# oresat-c3-v1_WRONG_FTDI.net
KiCad netlist of a schematic drawn in EAGLE
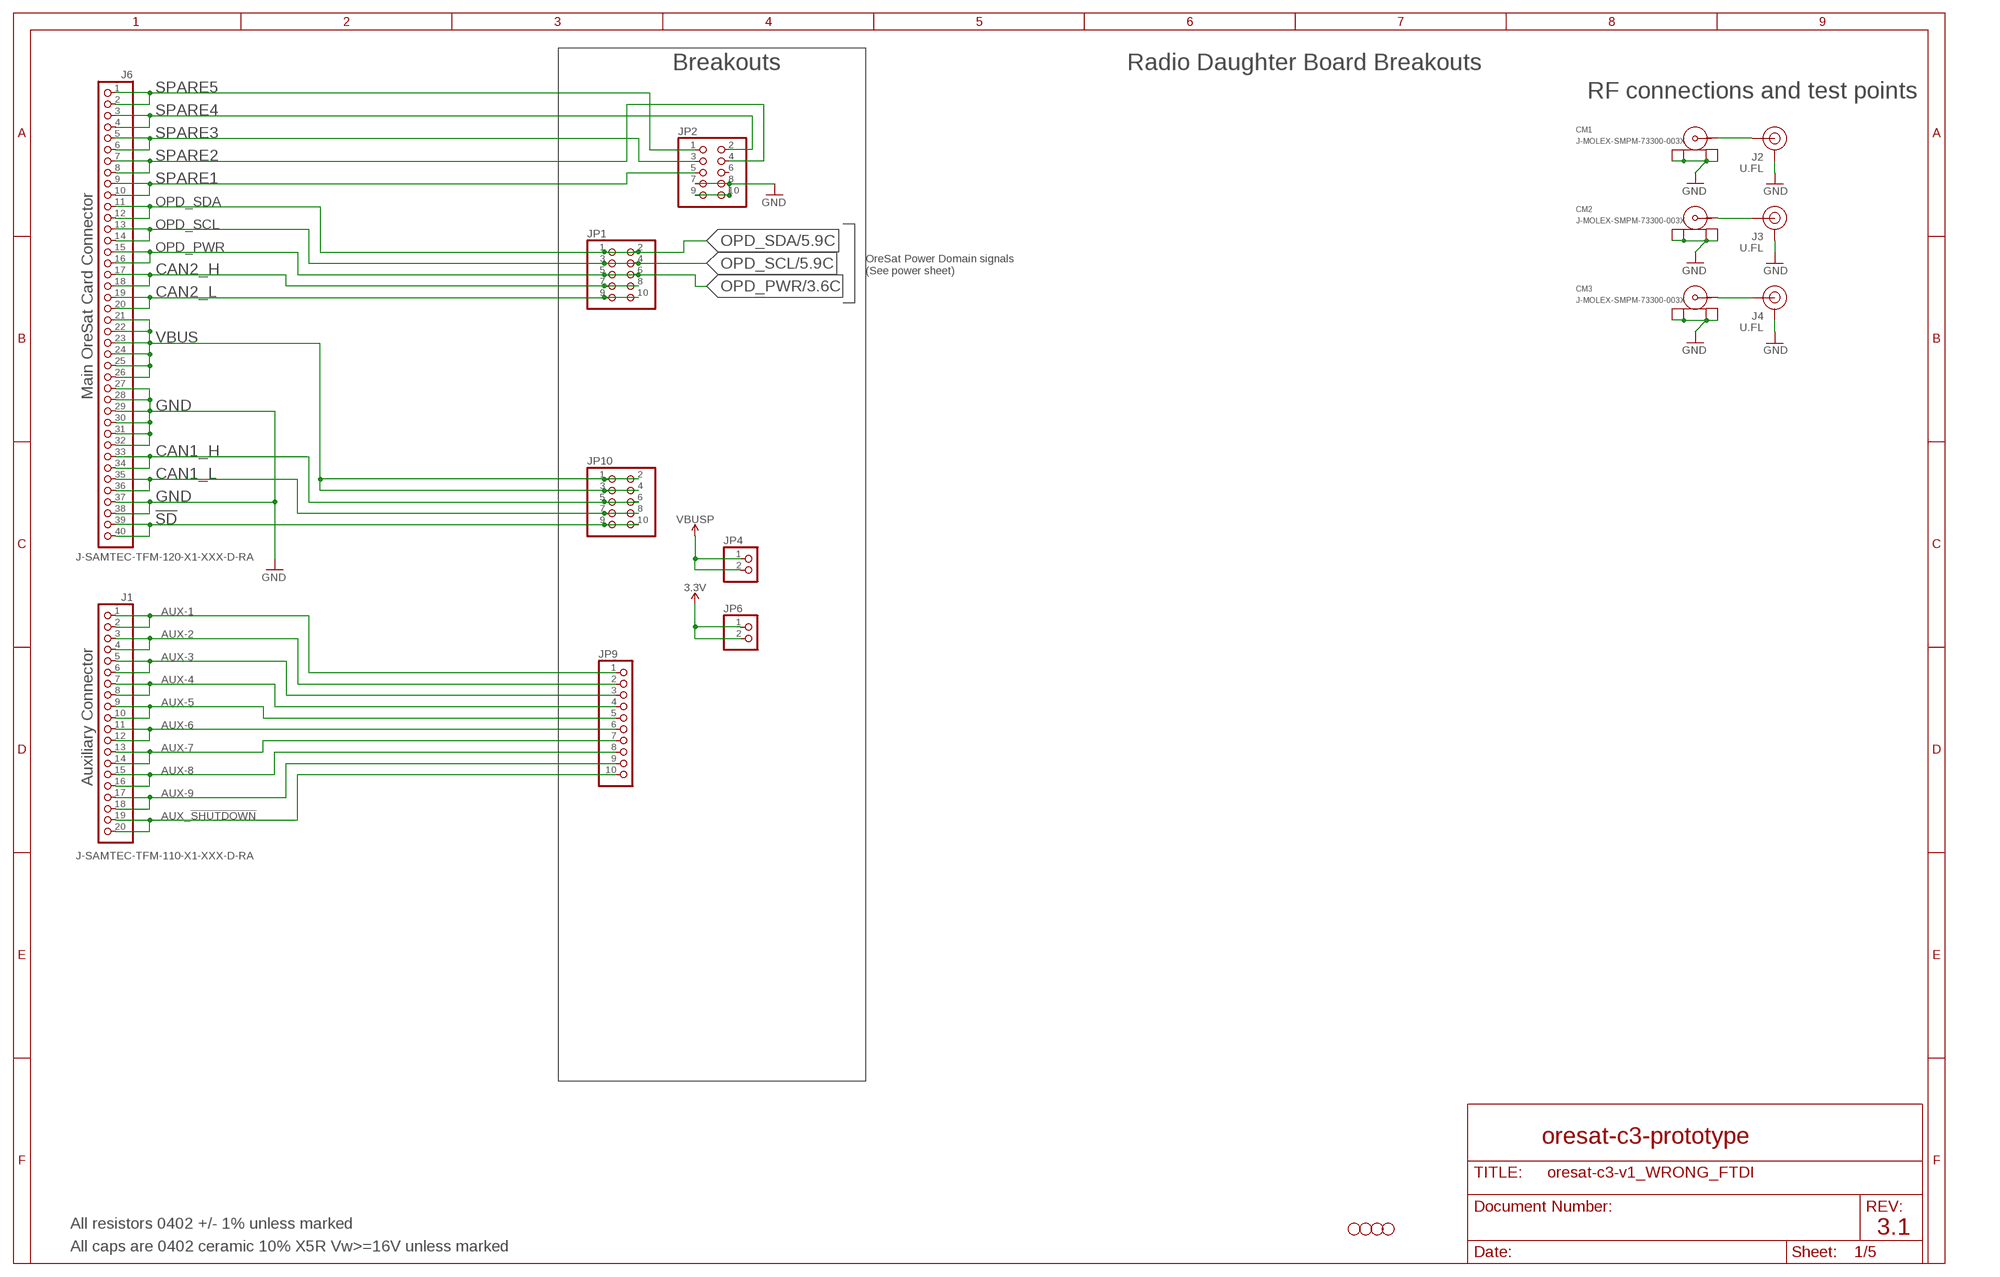
[diagram p0: schematic, sheet 1]
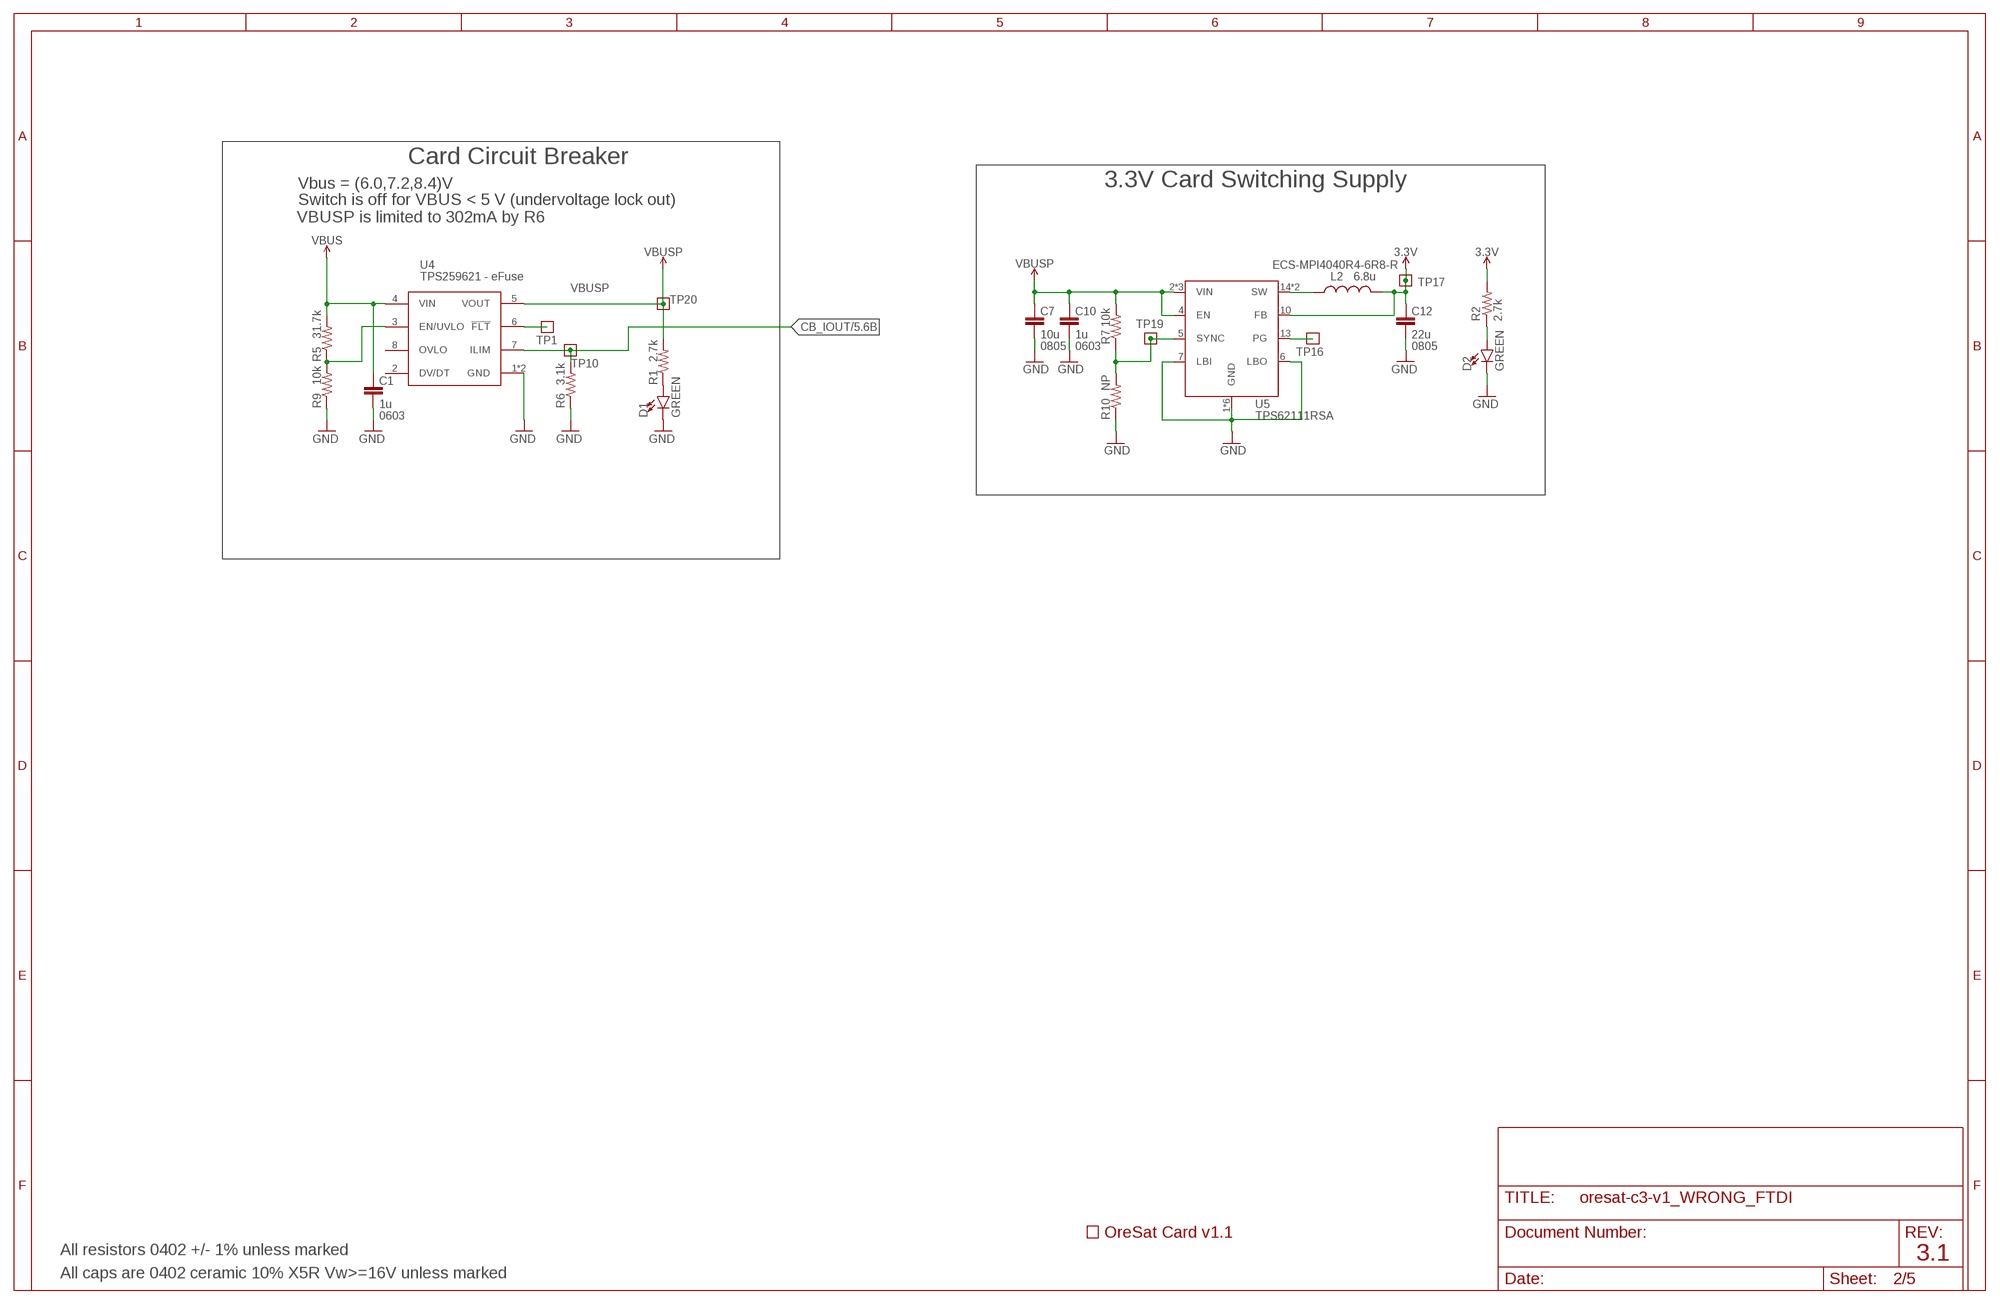
[diagram p1: schematic, sheet 2]
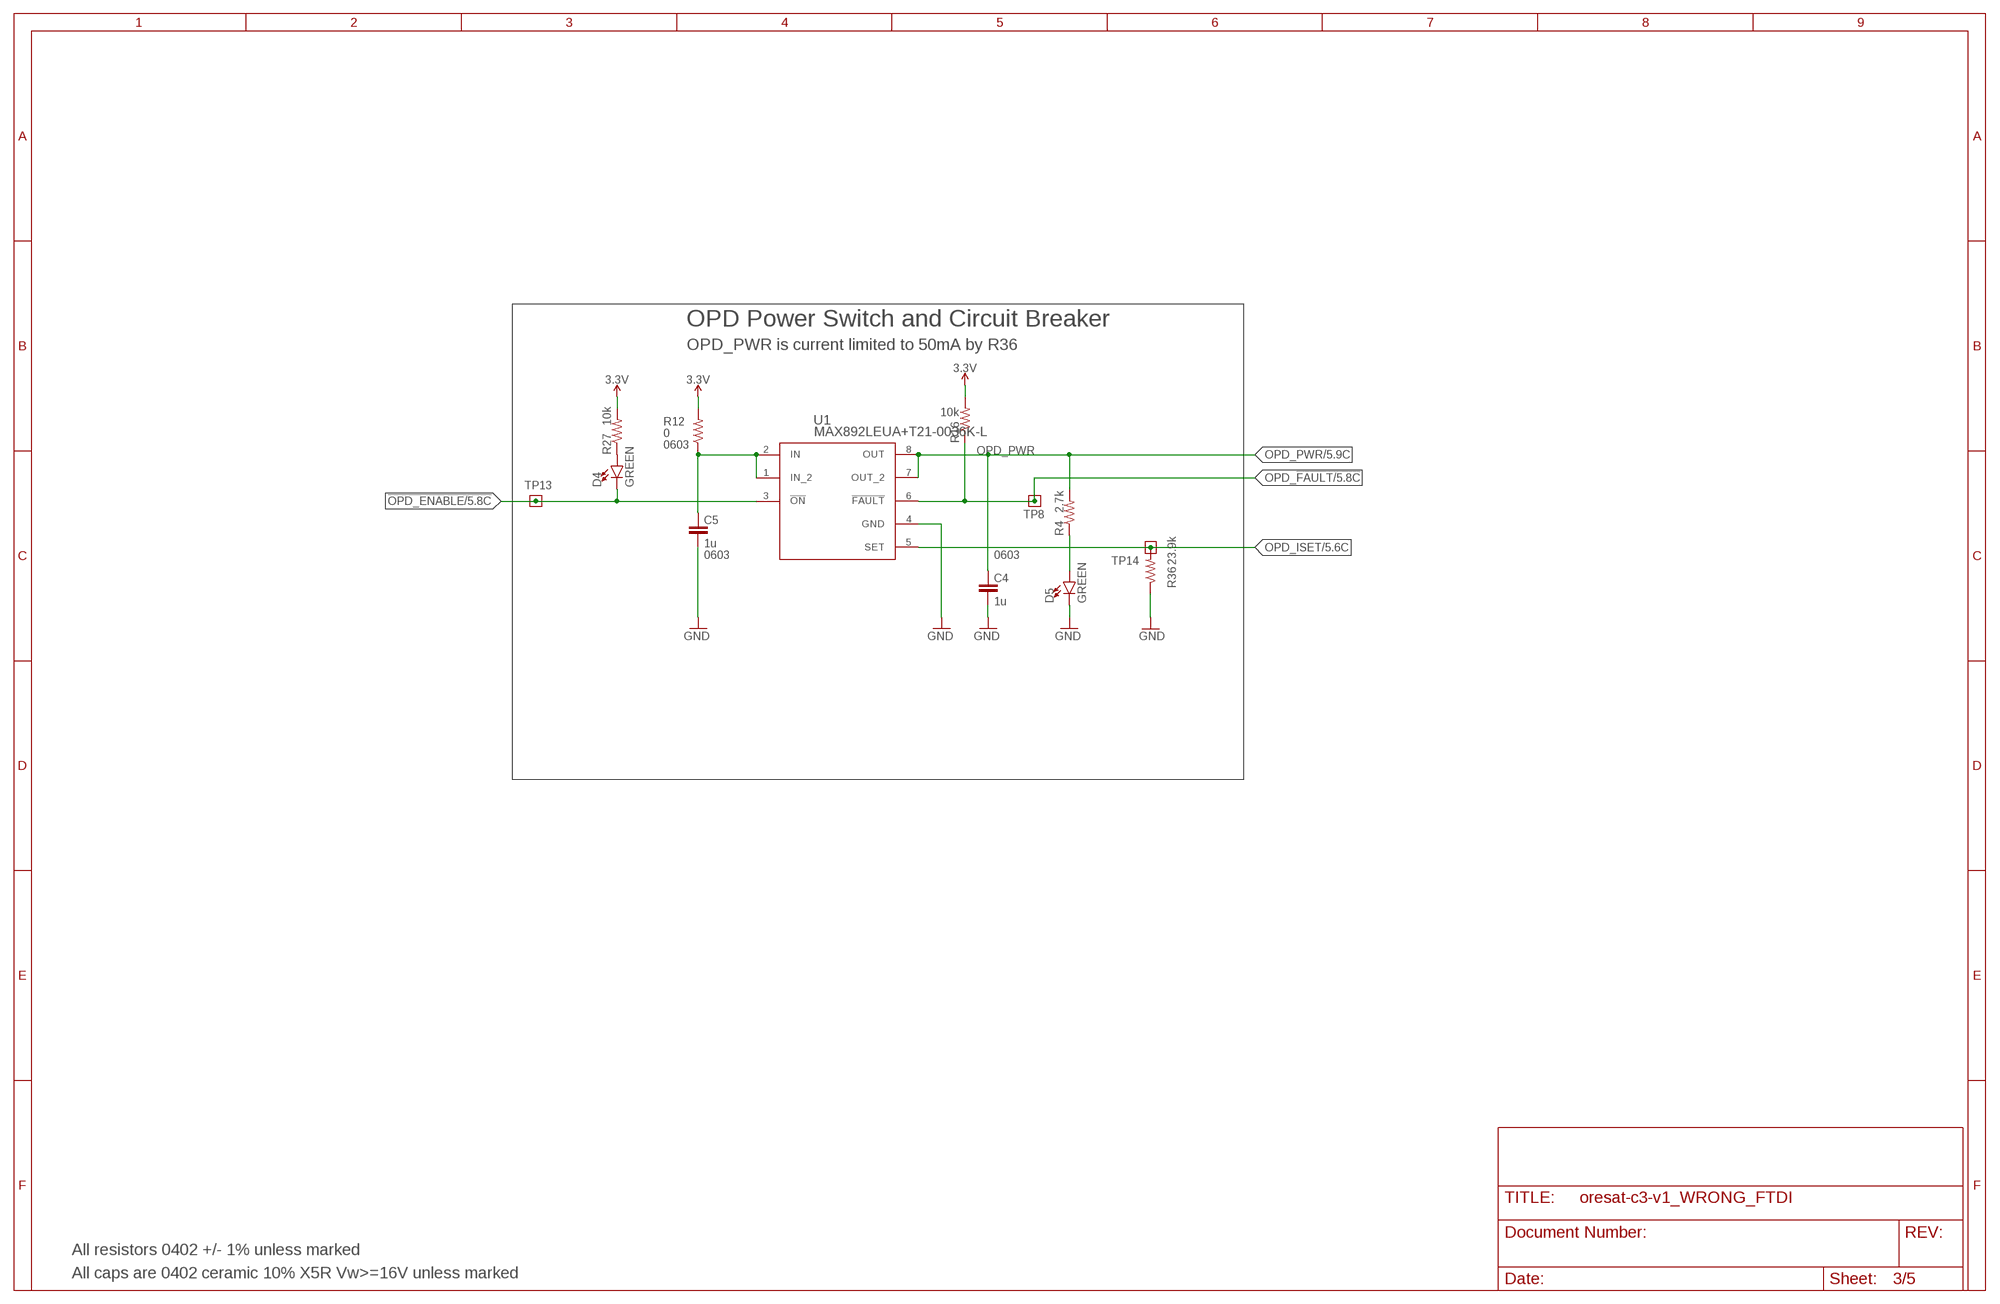
[diagram p2: schematic, sheet 3]
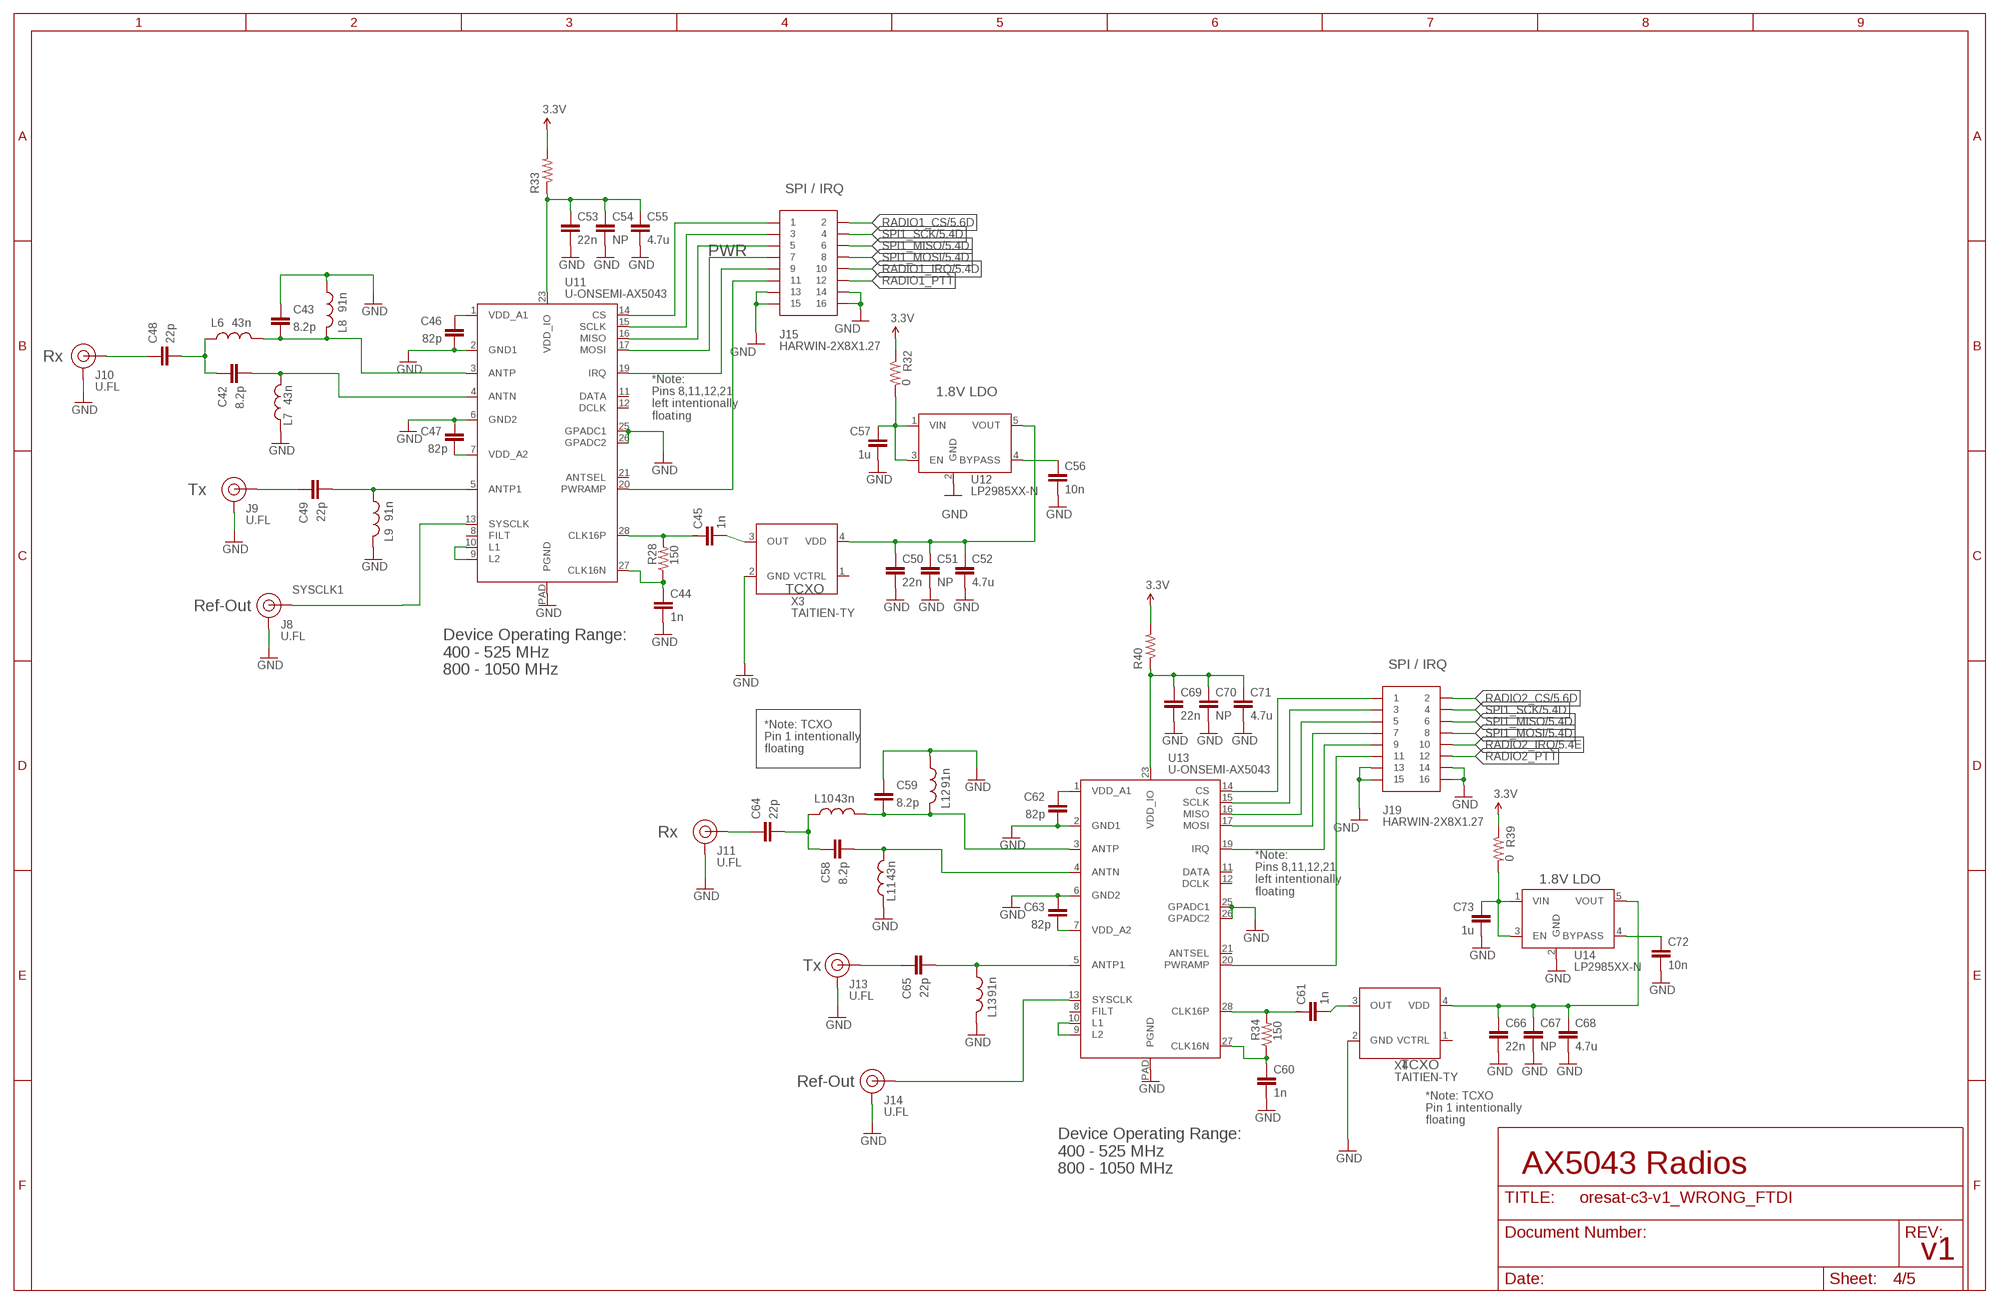
[diagram p3: schematic, sheet 4]
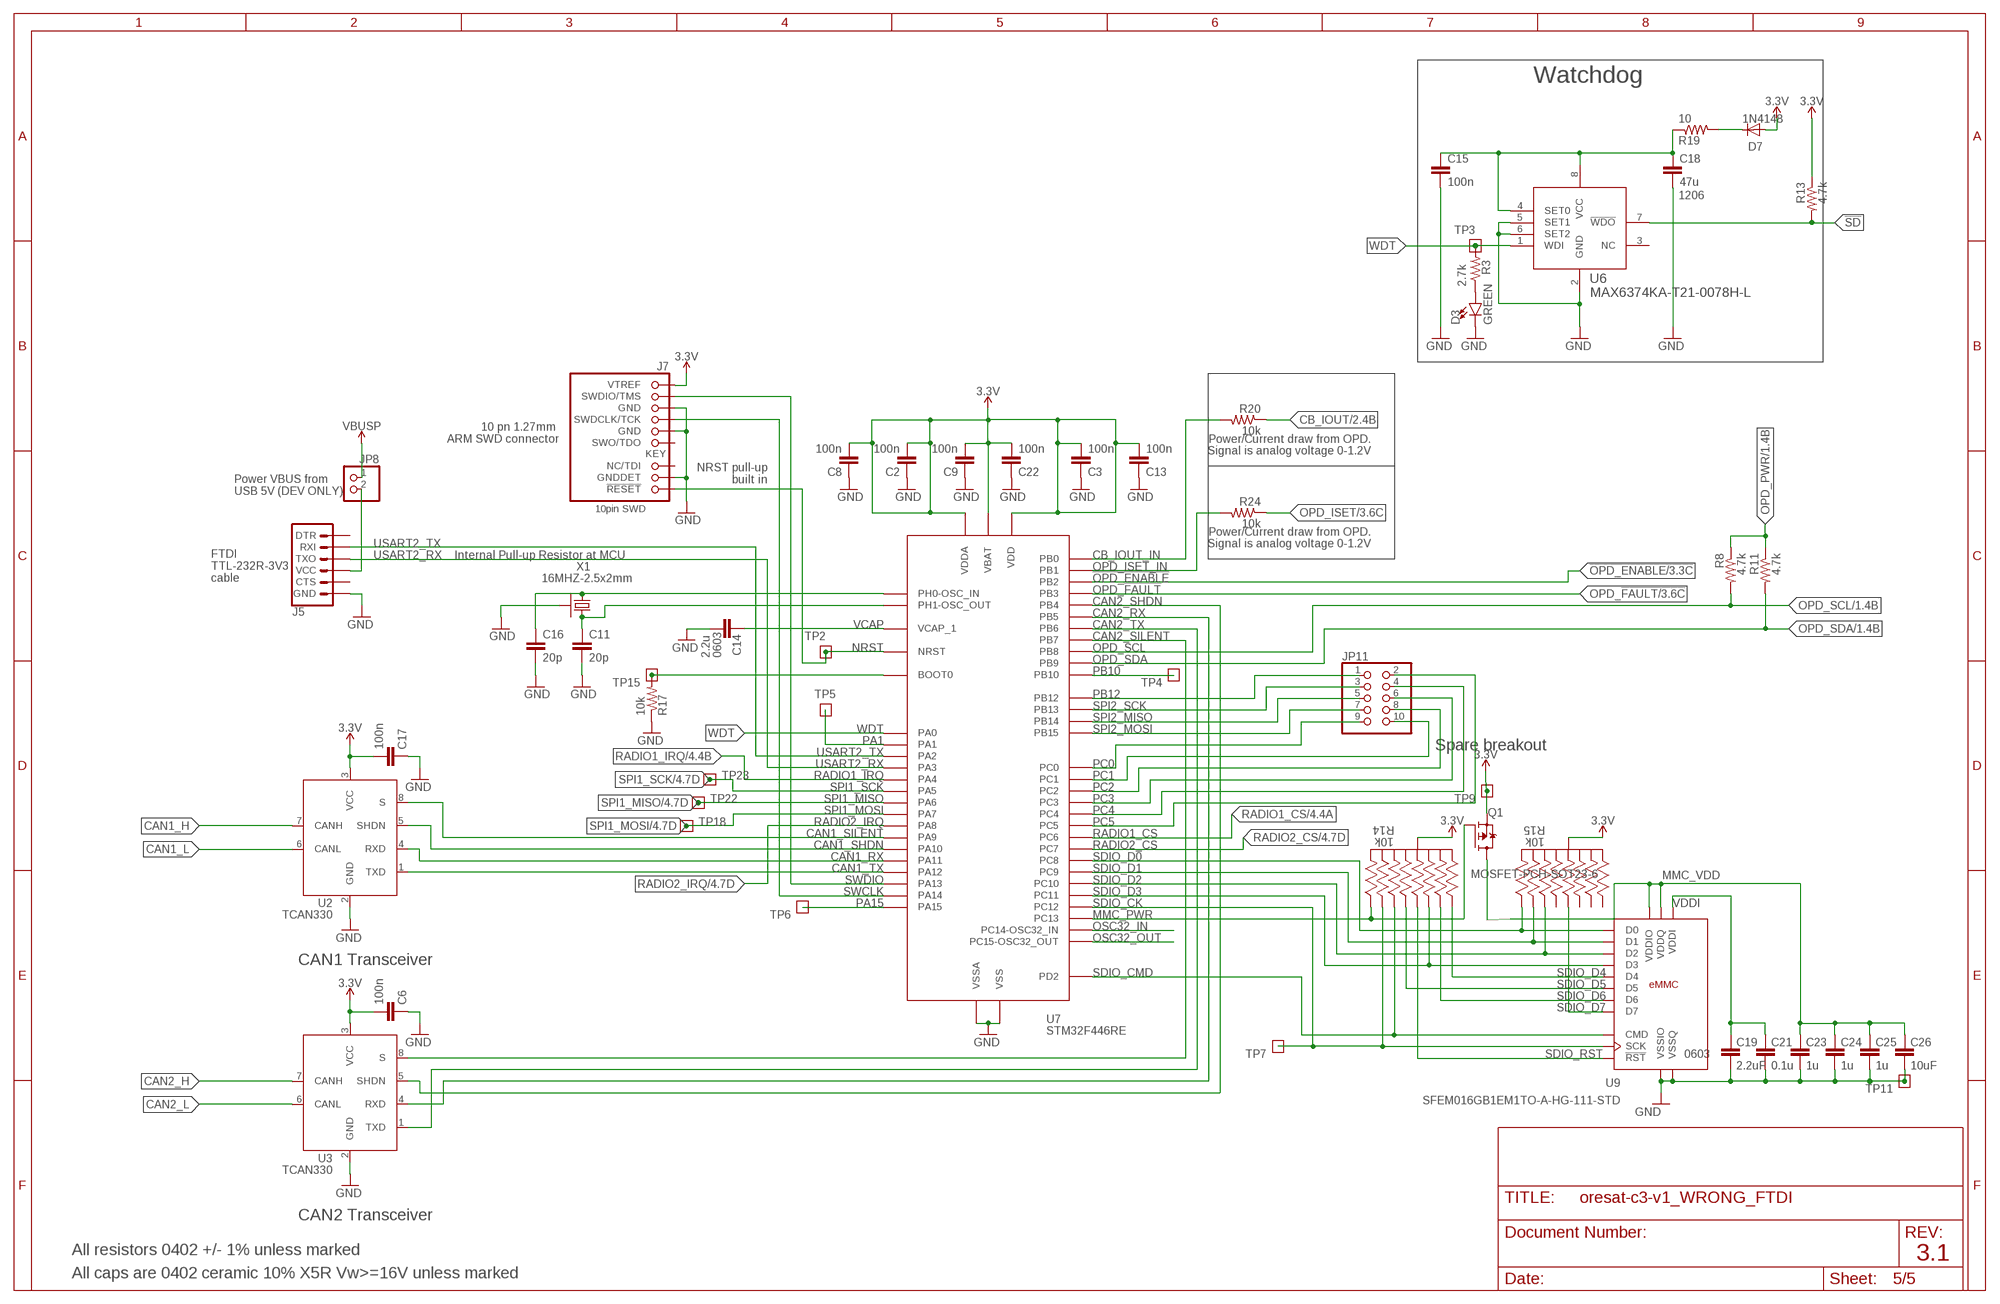
[diagram p4: schematic, sheet 5]

(export (version "E")
  (design (tool "Eeschema 10.0.6"))
  (components
    (comp (ref "C4")
      (value "1u")
      (footprint "eagle-import:.0603-B-NOSILK")
      (fields (field (name "MFR") "Samsung") (field (name "MPN") "CL05B104KO5NNNC"))
      (libsource (lib "eagle-import") (part "C-EU0603-B-NOSILK"))
    )
    (comp (ref "C5")
      (value "1u")
      (footprint "eagle-import:.0603-B-NOSILK")
      (fields (field (name "MFR") "Samsung") (field (name "MPN") "CL05B104KO5NNNC"))
      (libsource (lib "eagle-import") (part "C-EU0603-B-NOSILK"))
    )
    (comp (ref "D4")
      (value "GREEN")
      (footprint "eagle-import:LED-0603")
      (libsource (lib "eagle-import") (part "LED-GREEN0603"))
    )
    (comp (ref "D5")
      (value "GREEN")
      (footprint "eagle-import:LED-0603")
      (libsource (lib "eagle-import") (part "LED-GREEN0603"))
    )
    (comp (ref "R4")
      (value "2.7k")
      (footprint "eagle-import:.0402-B-NOSILK")
      (fields (field (name "MFR") "Samsung") (field (name "MPN") "RC1005F6653CS"))
      (libsource (lib "eagle-import") (part "R-US_0402-B-NOSILK"))
    )
    (comp (ref "R12")
      (value "0")
      (footprint "eagle-import:.0603-B-NOSILK")
      (fields (field (name "MFR") "Samsung") (field (name "MPN") "RC1005F6653CS"))
      (libsource (lib "eagle-import") (part "R-US_0603-B-NOSILK"))
    )
    (comp (ref "R16")
      (value "10k")
      (footprint "eagle-import:.0402-B-NOSILK")
      (fields (field (name "MFR") "Samsung") (field (name "MPN") "RC1005F6653CS"))
      (libsource (lib "eagle-import") (part "R-US_0402-B-NOSILK"))
    )
    (comp (ref "R27")
      (value "10k")
      (footprint "eagle-import:.0402-B-NOSILK")
      (fields (field (name "MFR") "Samsung") (field (name "MPN") "RC1005F6653CS"))
      (libsource (lib "eagle-import") (part "R-US_0402-B-NOSILK"))
    )
    (comp (ref "R36")
      (value "23.9k")
      (footprint "eagle-import:.0402-B-NOSILK")
      (fields (field (name "MFR") "Samsung") (field (name "MPN") "RC1005F6653CS"))
      (libsource (lib "eagle-import") (part "R-US_0402-B-NOSILK"))
    )
    (comp (ref "TP8")
      (value "TEST-POINT")
      (footprint "eagle-import:2MM-TEST-POINT")
      (libsource (lib "eagle-import") (part "TEST-POINT"))
    )
    (comp (ref "TP13")
      (value "TEST-POINT")
      (footprint "eagle-import:2MM-TEST-POINT")
      (libsource (lib "eagle-import") (part "TEST-POINT"))
    )
    (comp (ref "TP14")
      (value "TEST-POINT")
      (footprint "eagle-import:2MM-TEST-POINT")
      (libsource (lib "eagle-import") (part "TEST-POINT"))
    )
    (comp (ref "U1")
      (value "MAX892LEUA+T21-0036K-L")
      (footprint "eagle-import:21-0036K-L")
      (fields (field (name "MANUFACTURER_PART_NUMBER") "MAX892LEUA+T"))
      (libsource (lib "eagle-import") (part "MAX892LEUA+T21-0036K-L"))
    )
    (comp (ref "C1")
      (value "1u")
      (footprint "eagle-import:.0603-B-NOSILK")
      (fields (field (name "MFR") "Samsung") (field (name "MPN") "CL05B104KO5NNNC"))
      (libsource (lib "eagle-import") (part "C-EU0603-B-NOSILK"))
    )
    (comp (ref "C7")
      (value "10u")
      (footprint "eagle-import:.0805-B-NOSILK")
      (libsource (lib "eagle-import") (part "C-EU0805-B-NOSILK"))
    )
    (comp (ref "C10")
      (value "1u")
      (footprint "eagle-import:.0603-B-NOSILK")
      (fields (field (name "MFR") "Samsung") (field (name "MPN") "CL05B104KO5NNNC"))
      (libsource (lib "eagle-import") (part "C-EU0603-B-NOSILK"))
    )
    (comp (ref "C12")
      (value "22u")
      (footprint "eagle-import:.0805-B-NOSILK")
      (libsource (lib "eagle-import") (part "C-EU0805-B-NOSILK"))
    )
    (comp (ref "D1")
      (value "GREEN")
      (footprint "eagle-import:LED-0603")
      (libsource (lib "eagle-import") (part "LED-GREEN0603"))
    )
    (comp (ref "D2")
      (value "GREEN")
      (footprint "eagle-import:LED-0603")
      (libsource (lib "eagle-import") (part "LED-GREEN0603"))
    )
    (comp (ref "L2")
      (value "6.8u")
      (footprint "eagle-import:ECS-MPI4040")
      (fields (field (name "MFR") "ECS") (field (name "MPN") "ECS-MPI4040R4-6R8-R"))
      (libsource (lib "eagle-import") (part "L-ECS-MPI4040"))
    )
    (comp (ref "R1")
      (value "2.7k")
      (footprint "eagle-import:.0402-B-NOSILK")
      (fields (field (name "MFR") "Samsung") (field (name "MPN") "RC1005F6653CS"))
      (libsource (lib "eagle-import") (part "R-US_0402-B-NOSILK"))
    )
    (comp (ref "R2")
      (value "2.7k")
      (footprint "eagle-import:.0402-B-NOSILK")
      (fields (field (name "MFR") "Samsung") (field (name "MPN") "RC1005F6653CS"))
      (libsource (lib "eagle-import") (part "R-US_0402-B-NOSILK"))
    )
    (comp (ref "R5")
      (value "31.7k")
      (footprint "eagle-import:.0402-B-NOSILK")
      (fields (field (name "MFR") "Samsung") (field (name "MPN") "RC1005F6653CS"))
      (libsource (lib "eagle-import") (part "R-US_0402-B-NOSILK"))
    )
    (comp (ref "R6")
      (value "3.1k")
      (footprint "eagle-import:.0402-B-NOSILK")
      (fields (field (name "MFR") "Samsung") (field (name "MPN") "RC1005F6653CS"))
      (libsource (lib "eagle-import") (part "R-US_0402-B-NOSILK"))
    )
    (comp (ref "R7")
      (value "10k")
      (footprint "eagle-import:.0402-B-NOSILK")
      (fields (field (name "MFR") "Samsung") (field (name "MPN") "RC1005F6653CS"))
      (libsource (lib "eagle-import") (part "R-US_0402-B-NOSILK"))
    )
    (comp (ref "R9")
      (value "10k")
      (footprint "eagle-import:.0402-B-NOSILK")
      (fields (field (name "MFR") "Samsung") (field (name "MPN") "RC1005F6653CS"))
      (libsource (lib "eagle-import") (part "R-US_0402-B-NOSILK"))
    )
    (comp (ref "R10")
      (value "NP")
      (footprint "eagle-import:.0402-B-NOSILK")
      (fields (field (name "MFR") "Samsung") (field (name "MPN") "RC1005F6653CS"))
      (libsource (lib "eagle-import") (part "R-US_0402-B-NOSILK"))
    )
    (comp (ref "TP1")
      (value "TEST-POINT")
      (footprint "eagle-import:2MM-TEST-POINT")
      (libsource (lib "eagle-import") (part "TEST-POINT"))
    )
    (comp (ref "TP10")
      (value "TEST-POINT")
      (footprint "eagle-import:2MM-TEST-POINT")
      (libsource (lib "eagle-import") (part "TEST-POINT"))
    )
    (comp (ref "TP16")
      (value "TEST-POINT")
      (footprint "eagle-import:2MM-TEST-POINT")
      (libsource (lib "eagle-import") (part "TEST-POINT"))
    )
    (comp (ref "TP17")
      (value "TEST-POINT")
      (footprint "eagle-import:2MM-TEST-POINT")
      (libsource (lib "eagle-import") (part "TEST-POINT"))
    )
    (comp (ref "TP19")
      (value "TEST-POINT")
      (footprint "eagle-import:2MM-TEST-POINT")
      (libsource (lib "eagle-import") (part "TEST-POINT"))
    )
    (comp (ref "TP20")
      (value "TEST-POINT")
      (footprint "eagle-import:2MM-TEST-POINT")
      (libsource (lib "eagle-import") (part "TEST-POINT"))
    )
    (comp (ref "U$1")
      (value "ORESAT-CARD-V1.1-3XRF")
      (footprint "eagle-import:ORESAT-CARD-V1.1-3XRF")
      (libsource (lib "eagle-import") (part "ORESAT-CARD-V1.1-3XRF"))
    )
    (comp (ref "U4")
      (value "TPS259621 - eFuse")
      (footprint "eagle-import:SO-POWERPAD-8")
      (libsource (lib "eagle-import") (part "TPS2596XX"))
    )
    (comp (ref "U5")
      (value "TPS62111RSA")
      (footprint "eagle-import:S-PVQFN-16")
      (fields (field (name "MFR") "TI"))
      (libsource (lib "eagle-import") (part "TPS6211X"))
    )
    (comp (ref "CM1")
      (value "J-MOLEX-SMPM-73300-003X")
      (footprint "eagle-import:J-MOLEX-SMPM-073300-003X")
      (fields (field (name "MFR") "Molex") (field (name "MPN") "73300-0020"))
      (libsource (lib "eagle-import") (part "J-MOLEX-SMPM-73300-003X"))
    )
    (comp (ref "CM2")
      (value "J-MOLEX-SMPM-73300-003X")
      (footprint "eagle-import:J-MOLEX-SMPM-073300-003X")
      (fields (field (name "MFR") "Molex") (field (name "MPN") "73300-0020"))
      (libsource (lib "eagle-import") (part "J-MOLEX-SMPM-73300-003X"))
    )
    (comp (ref "CM3")
      (value "J-MOLEX-SMPM-73300-003X")
      (footprint "eagle-import:J-MOLEX-SMPM-073300-003X")
      (fields (field (name "MFR") "Molex") (field (name "MPN") "73300-0020"))
      (libsource (lib "eagle-import") (part "J-MOLEX-SMPM-73300-003X"))
    )
    (comp (ref "H1")
      (value "STAND-OFFTIGHT")
      (footprint "eagle-import:STAND-OFF-TIGHT")
      (libsource (lib "eagle-import") (part "STAND-OFFTIGHT"))
    )
    (comp (ref "H2")
      (value "STAND-OFFTIGHT")
      (footprint "eagle-import:STAND-OFF-TIGHT")
      (libsource (lib "eagle-import") (part "STAND-OFFTIGHT"))
    )
    (comp (ref "H3")
      (value "STAND-OFFTIGHT")
      (footprint "eagle-import:STAND-OFF-TIGHT")
      (libsource (lib "eagle-import") (part "STAND-OFFTIGHT"))
    )
    (comp (ref "H4")
      (value "STAND-OFFTIGHT")
      (footprint "eagle-import:STAND-OFF-TIGHT")
      (libsource (lib "eagle-import") (part "STAND-OFFTIGHT"))
    )
    (comp (ref "J1")
      (value "J-SAMTEC-TFM-110-X1-XXX-D-RA")
      (footprint "eagle-import:J-SAMTEC-TFM-110-X1-XXX-D-RA")
      (fields (field (name "MFR") "Samtec") (field (name "MPN") "TFM-110-01-L-D-RA "))
      (libsource (lib "eagle-import") (part "J-SAMTEC-TFM-110-X1-XXX-D-RA"))
    )
    (comp (ref "J2")
      (value "U.FL")
      (footprint "eagle-import:U.FL")
      (libsource (lib "eagle-import") (part "U.FL2PIN"))
    )
    (comp (ref "J3")
      (value "U.FL")
      (footprint "eagle-import:U.FL")
      (libsource (lib "eagle-import") (part "U.FL2PIN"))
    )
    (comp (ref "J4")
      (value "U.FL")
      (footprint "eagle-import:U.FL")
      (libsource (lib "eagle-import") (part "U.FL2PIN"))
    )
    (comp (ref "J6")
      (value "J-SAMTEC-TFM-120-X1-XXX-D-RA")
      (footprint "eagle-import:J-SAMTEC-TFM-120-X1-XXX-D-RA")
      (fields (field (name "MFR") "Samtec") (field (name "MPN") "TFM-120-01-L-D-RA"))
      (libsource (lib "eagle-import") (part "J-SAMTEC-TFM-120-X1-XXX-D-RA"))
    )
    (comp (ref "JP1")
      (value "PINHD-2X5")
      (footprint "eagle-import:2X05")
      (libsource (lib "eagle-import") (part "PINHD-2X5"))
    )
    (comp (ref "JP2")
      (value "PINHD-2X5")
      (footprint "eagle-import:2X05")
      (libsource (lib "eagle-import") (part "PINHD-2X5"))
    )
    (comp (ref "JP4")
      (value "PINHD-1X2")
      (footprint "eagle-import:1X02")
      (libsource (lib "eagle-import") (part "PINHD-1X2"))
    )
    (comp (ref "JP6")
      (value "PINHD-1X2")
      (footprint "eagle-import:1X02")
      (libsource (lib "eagle-import") (part "PINHD-1X2"))
    )
    (comp (ref "JP9")
      (value "PINHD-1X10")
      (footprint "eagle-import:1X10")
      (libsource (lib "eagle-import") (part "PINHD-1X10"))
    )
    (comp (ref "JP10")
      (value "PINHD-2X5")
      (footprint "eagle-import:2X05")
      (libsource (lib "eagle-import") (part "PINHD-2X5"))
    )
    (comp (ref "C2")
      (value "100n")
      (footprint "eagle-import:.0402-B-NOSILK")
      (fields (field (name "MFR") "Samsung") (field (name "MPN") "CL05B104KO5NNNC"))
      (libsource (lib "eagle-import") (part "C-EU0402-B-NOSILK"))
    )
    (comp (ref "C3")
      (value "100n")
      (footprint "eagle-import:.0402-B-NOSILK")
      (fields (field (name "MFR") "Samsung") (field (name "MPN") "CL05B104KO5NNNC"))
      (libsource (lib "eagle-import") (part "C-EU0402-B-NOSILK"))
    )
    (comp (ref "C6")
      (value "100n")
      (footprint "eagle-import:.0402-B-NOSILK")
      (fields (field (name "MFR") "Samsung") (field (name "MPN") "CL05B104KO5NNNC"))
      (libsource (lib "eagle-import") (part "C-EU0402-B-NOSILK"))
    )
    (comp (ref "C8")
      (value "100n")
      (footprint "eagle-import:.0402-B-NOSILK")
      (fields (field (name "MFR") "Samsung") (field (name "MPN") "CL05B104KO5NNNC"))
      (libsource (lib "eagle-import") (part "C-EU0402-B-NOSILK"))
    )
    (comp (ref "C9")
      (value "100n")
      (footprint "eagle-import:.0402-B-NOSILK")
      (fields (field (name "MFR") "Samsung") (field (name "MPN") "CL05B104KO5NNNC"))
      (libsource (lib "eagle-import") (part "C-EU0402-B-NOSILK"))
    )
    (comp (ref "C11")
      (value "20p")
      (footprint "eagle-import:.0402-B-NOSILK")
      (fields (field (name "MFR") "Samsung") (field (name "MPN") "CL05C200JB51PNC"))
      (libsource (lib "eagle-import") (part "rcl_custom_C-EU0402-B-NOSILK"))
    )
    (comp (ref "C13")
      (value "100n")
      (footprint "eagle-import:.0402-B-NOSILK")
      (fields (field (name "MFR") "Samsung") (field (name "MPN") "CL05B104KO5NNNC"))
      (libsource (lib "eagle-import") (part "C-EU0402-B-NOSILK"))
    )
    (comp (ref "C14")
      (value "2.2u")
      (footprint "eagle-import:.0603-B-NOSILK")
      (fields (field (name "MFR") "Samsung") (field (name "MPN") "CL05B104KO5NNNC"))
      (libsource (lib "eagle-import") (part "C-EU0603-B-NOSILK"))
    )
    (comp (ref "C15")
      (value "100n")
      (footprint "eagle-import:.0402-B-NOSILK")
      (fields (field (name "MFR") "Samsung") (field (name "MPN") "CL05C200JB51PNC"))
      (libsource (lib "eagle-import") (part "C-EU0402-B-NOSILK"))
    )
    (comp (ref "C16")
      (value "20p")
      (footprint "eagle-import:.0402-B-NOSILK")
      (fields (field (name "MFR") "Samsung") (field (name "MPN") "CL05C200JB51PNC"))
      (libsource (lib "eagle-import") (part "C-EU0402-B-NOSILK"))
    )
    (comp (ref "C17")
      (value "100n")
      (footprint "eagle-import:.0402-B-NOSILK")
      (fields (field (name "MFR") "Samsung") (field (name "MPN") "CL05B104KO5NNNC"))
      (libsource (lib "eagle-import") (part "C-EU0402-B-NOSILK"))
    )
    (comp (ref "C18")
      (value "47u")
      (footprint "eagle-import:1206-B")
      (fields (field (name "MFR") "Samsung") (field (name "MPN") "CL05C200JB51PNC"))
      (libsource (lib "eagle-import") (part "C-EU1206-B"))
    )
    (comp (ref "C19")
      (value "2.2uF")
      (footprint "eagle-import:.0603-B-NOSILK")
      (fields (field (name "MFR") "Samsung") (field (name "MPN") "CL05B104KO5NNNC"))
      (libsource (lib "eagle-import") (part "C-EU0603-B-NOSILK"))
    )
    (comp (ref "C21")
      (value "0.1u")
      (footprint "eagle-import:.0603-B-NOSILK")
      (fields (field (name "MFR") "Samsung") (field (name "MPN") "CL05B104KO5NNNC"))
      (libsource (lib "eagle-import") (part "C-EU0603-B-NOSILK"))
    )
    (comp (ref "C22")
      (value "100n")
      (footprint "eagle-import:.0402-B-NOSILK")
      (fields (field (name "MFR") "Samsung") (field (name "MPN") "CL05B104KO5NNNC"))
      (libsource (lib "eagle-import") (part "C-EU0402-B-NOSILK"))
    )
    (comp (ref "C23")
      (value "1u")
      (footprint "eagle-import:.0603-B-NOSILK")
      (fields (field (name "MFR") "Samsung") (field (name "MPN") "CL05B104KO5NNNC"))
      (libsource (lib "eagle-import") (part "C-EU0603-B-NOSILK"))
    )
    (comp (ref "C24")
      (value "1u")
      (footprint "eagle-import:.0603-B-NOSILK")
      (fields (field (name "MFR") "Samsung") (field (name "MPN") "CL05B104KO5NNNC"))
      (libsource (lib "eagle-import") (part "C-EU0603-B-NOSILK"))
    )
    (comp (ref "C25")
      (value "1u")
      (footprint "eagle-import:.0603-B-NOSILK")
      (fields (field (name "MFR") "Samsung") (field (name "MPN") "CL05B104KO5NNNC"))
      (libsource (lib "eagle-import") (part "C-EU0603-B-NOSILK"))
    )
    (comp (ref "C26")
      (value "10uF")
      (footprint "eagle-import:.0603-B-NOSILK")
      (fields (field (name "MFR") "Samsung") (field (name "MPN") "CL05B104KO5NNNC"))
      (libsource (lib "eagle-import") (part "C-EU0603-B-NOSILK"))
    )
    (comp (ref "D3")
      (value "GREEN")
      (footprint "eagle-import:LED-0603")
      (libsource (lib "eagle-import") (part "LED-GREEN0603"))
    )
    (comp (ref "D7")
      (value "1N4148")
      (footprint "eagle-import:SOD-323")
      (libsource (lib "eagle-import") (part "DIODESOD"))
    )
    (comp (ref "J5")
      (value "6_PIN_SERIAL_TARGETSILK")
      (footprint "eagle-import:6_PIN_SERIAL_TARGET_SIDE_W_SILK")
      (libsource (lib "eagle-import") (part "6_PIN_SERIAL_TARGETSILK"))
    )
    (comp (ref "J7")
      (value "FTSH-105-XX-X-DV-K")
      (footprint "eagle-import:CON10_2X5_DUK_FTSH")
      (fields (field (name "MFR") "Samtec") (field (name "MPN") "FTSH-105-01-F-DV-K"))
      (libsource (lib "eagle-import") (part "FTSH-105-XX-X-DV-K"))
    )
    (comp (ref "JP8")
      (value "PINHD-1X2")
      (footprint "eagle-import:1X02")
      (libsource (lib "eagle-import") (part "pinhead_325_PINHD-1X2"))
    )
    (comp (ref "JP11")
      (value "PINHD-2X5")
      (footprint "eagle-import:2X05")
      (libsource (lib "eagle-import") (part "PINHD-2X5"))
    )
    (comp (ref "Q1")
      (value "MOSFET-PCH-SOT23-6")
      (footprint "eagle-import:SOT23-6")
      (libsource (lib "eagle-import") (part "MOSFET-PCH-SOT23-6"))
    )
    (comp (ref "R3")
      (value "2.7k")
      (footprint "eagle-import:.0402-B-NOSILK")
      (fields (field (name "MFR") "Samsung") (field (name "MPN") "RC1005F6653CS"))
      (libsource (lib "eagle-import") (part "R-US_0402-B-NOSILK"))
    )
    (comp (ref "R8")
      (value "4.7k")
      (footprint "eagle-import:.0402-B-NOSILK")
      (libsource (lib "eagle-import") (part "R-US_0402-B-NOSILK"))
    )
    (comp (ref "R11")
      (value "4.7k")
      (footprint "eagle-import:.0402-B-NOSILK")
      (libsource (lib "eagle-import") (part "R-US_0402-B-NOSILK"))
    )
    (comp (ref "R13")
      (value "4.7k")
      (footprint "eagle-import:.0402-B-NOSILK")
      (libsource (lib "eagle-import") (part "R-US_0402-B-NOSILK"))
    )
    (comp (ref "R14")
      (value "10k")
      (footprint "eagle-import:ARRAY_EXBA-M")
      (fields (field (name "MANUFACTURER_PART_NUMBER") "EXBA10P391J"))
      (libsource (lib "eagle-import") (part "EXB-A10P391JC_ARRAY_EXBA-M"))
    )
    (comp (ref "R15")
      (value "10k")
      (footprint "eagle-import:ARRAY_EXBA-M")
      (fields (field (name "MANUFACTURER_PART_NUMBER") "EXBA10P391J"))
      (libsource (lib "eagle-import") (part "EXB-A10P391JC_ARRAY_EXBA-M"))
    )
    (comp (ref "R17")
      (value "10k")
      (footprint "eagle-import:.0402-B-NOSILK")
      (fields (field (name "MFR") "Samsung") (field (name "MPN") "RC1005F6653CS"))
      (libsource (lib "eagle-import") (part "R-US_0402-B-NOSILK"))
    )
    (comp (ref "R19")
      (value "10")
      (footprint "eagle-import:.0402-B-NOSILK")
      (libsource (lib "eagle-import") (part "R-US_0402-B-NOSILK"))
    )
    (comp (ref "R20")
      (value "10k")
      (footprint "eagle-import:.0402-B-NOSILK")
      (libsource (lib "eagle-import") (part "R-US_0402-B-NOSILK"))
    )
    (comp (ref "R24")
      (value "10k")
      (footprint "eagle-import:.0402-B-NOSILK")
      (libsource (lib "eagle-import") (part "R-US_0402-B-NOSILK"))
    )
    (comp (ref "TP2")
      (value "TEST-POINT")
      (footprint "eagle-import:2MM-TEST-POINT")
      (libsource (lib "eagle-import") (part "TEST-POINT"))
    )
    (comp (ref "TP3")
      (value "TEST-POINT")
      (footprint "eagle-import:2MM-TEST-POINT")
      (libsource (lib "eagle-import") (part "TEST-POINT"))
    )
    (comp (ref "TP4")
      (value "TEST-POINT")
      (footprint "eagle-import:2MM-TEST-POINT")
      (libsource (lib "eagle-import") (part "TEST-POINT"))
    )
    (comp (ref "TP5")
      (value "TEST-POINT")
      (footprint "eagle-import:2MM-TEST-POINT")
      (libsource (lib "eagle-import") (part "TEST-POINT"))
    )
    (comp (ref "TP6")
      (value "TEST-POINT")
      (footprint "eagle-import:2MM-TEST-POINT")
      (libsource (lib "eagle-import") (part "TEST-POINT"))
    )
    (comp (ref "TP7")
      (value "TEST-POINT")
      (footprint "eagle-import:2MM-TEST-POINT")
      (libsource (lib "eagle-import") (part "TEST-POINT"))
    )
    (comp (ref "TP9")
      (value "TEST-POINT")
      (footprint "eagle-import:2MM-TEST-POINT")
      (libsource (lib "eagle-import") (part "TEST-POINT"))
    )
    (comp (ref "TP11")
      (value "TEST-POINT")
      (footprint "eagle-import:2MM-TEST-POINT")
      (libsource (lib "eagle-import") (part "TEST-POINT"))
    )
    (comp (ref "TP15")
      (value "TEST-POINT")
      (footprint "eagle-import:2MM-TEST-POINT")
      (libsource (lib "eagle-import") (part "TEST-POINT"))
    )
    (comp (ref "TP18")
      (value "TEST-POINT")
      (footprint "eagle-import:2MM-TEST-POINT")
      (libsource (lib "eagle-import") (part "TEST-POINT"))
    )
    (comp (ref "TP22")
      (value "TEST-POINT")
      (footprint "eagle-import:2MM-TEST-POINT")
      (libsource (lib "eagle-import") (part "TEST-POINT"))
    )
    (comp (ref "TP23")
      (value "TEST-POINT")
      (footprint "eagle-import:2MM-TEST-POINT")
      (libsource (lib "eagle-import") (part "TEST-POINT"))
    )
    (comp (ref "U2")
      (value "TCAN330")
      (footprint "eagle-import:SOT23-8_TI-DCN")
      (fields (field (name "MFR") "Texas Instruments") (field (name "MPN") "TCAN330GDCNT"))
      (libsource (lib "eagle-import") (part "TCAN330"))
    )
    (comp (ref "U3")
      (value "TCAN330")
      (footprint "eagle-import:SOT23-8_TI-DCN")
      (fields (field (name "MFR") "Texas Instruments") (field (name "MPN") "TCAN330GDCNT"))
      (libsource (lib "eagle-import") (part "TCAN330"))
    )
    (comp (ref "U6")
      (value "MAX6374KA-T21-0078H-L")
      (footprint "eagle-import:21-0078H-L")
      (fields (field (name "MANUFACTURER_PART_NUMBER") "max6374kat"))
      (libsource (lib "eagle-import") (part "MAX6374KA-T21-0078H-L"))
    )
    (comp (ref "U7")
      (value "STM32F446RE")
      (footprint "eagle-import:QFP-10X10-64")
      (libsource (lib "eagle-import") (part "STM32F446RE"))
    )
    (comp (ref "U9")
      (value "SFEM016GB1EM1TO-A-HG-111-STD")
      (footprint "eagle-import:BGA-153(11.5X13)(EMMC-BA)")
      (libsource (lib "eagle-import") (part "EMMC+RESET-BA"))
    )
    (comp (ref "X1")
      (value "16MHZ-2.5x2mm")
      (footprint "eagle-import:CRYSTAL_2.5X2")
      (fields (field (name "MFR") "ECS Inc.") (field (name "MPN") "ECS-160-10-36Q-ES-TR"))
      (libsource (lib "eagle-import") (part "CRYSTAL-WITH-GND"))
    )
    (comp (ref "C42")
      (value "8.2p")
      (footprint "eagle-import:.0402-C-NOSILK")
      (libsource (lib "eagle-import") (part "C-EU0402-C-NOSILK"))
    )
    (comp (ref "C43")
      (value "8.2p")
      (footprint "eagle-import:.0402-C-NOSILK")
      (libsource (lib "eagle-import") (part "C-EU0402-C-NOSILK"))
    )
    (comp (ref "C44")
      (value "1n")
      (footprint "eagle-import:.0402-C-NOSILK")
      (libsource (lib "eagle-import") (part "C-EU0402-C-NOSILK"))
    )
    (comp (ref "C45")
      (value "1n")
      (footprint "eagle-import:.0402-C-NOSILK")
      (libsource (lib "eagle-import") (part "C-EU0402-C-NOSILK"))
    )
    (comp (ref "C46")
      (value "82p")
      (footprint "eagle-import:.0402-C-NOSILK")
      (libsource (lib "eagle-import") (part "C-EU0402-C-NOSILK"))
    )
    (comp (ref "C47")
      (value "82p")
      (footprint "eagle-import:.0402-C-NOSILK")
      (libsource (lib "eagle-import") (part "C-EU0402-C-NOSILK"))
    )
    (comp (ref "C48")
      (value "22p")
      (footprint "eagle-import:.0402-C-NOSILK")
      (libsource (lib "eagle-import") (part "C-EU0402-C-NOSILK"))
    )
    (comp (ref "C49")
      (value "22p")
      (footprint "eagle-import:.0402-C-NOSILK")
      (libsource (lib "eagle-import") (part "C-EU0402-C-NOSILK"))
    )
    (comp (ref "C50")
      (value "22n")
      (footprint "eagle-import:.0603-C-NOSILK")
      (libsource (lib "eagle-import") (part "C-EU0603-C-NOSILK"))
    )
    (comp (ref "C51")
      (value "NP")
      (footprint "eagle-import:.0603-C-NOSILK")
      (libsource (lib "eagle-import") (part "C-EU0603-C-NOSILK"))
    )
    (comp (ref "C52")
      (value "4.7u")
      (footprint "eagle-import:.0603-C-NOSILK")
      (libsource (lib "eagle-import") (part "C-EU0603-C-NOSILK"))
    )
    (comp (ref "C53")
      (value "22n")
      (footprint "eagle-import:.0603-C-NOSILK")
      (libsource (lib "eagle-import") (part "C-EU0603-C-NOSILK"))
    )
    (comp (ref "C54")
      (value "NP")
      (footprint "eagle-import:.0603-C-NOSILK")
      (libsource (lib "eagle-import") (part "C-EU0603-C-NOSILK"))
    )
    (comp (ref "C55")
      (value "4.7u")
      (footprint "eagle-import:.0603-C-NOSILK")
      (libsource (lib "eagle-import") (part "C-EU0603-C-NOSILK"))
    )
    (comp (ref "C56")
      (value "10n")
      (footprint "eagle-import:.0603-C-NOSILK")
      (libsource (lib "eagle-import") (part "C-EU0603-C-NOSILK"))
    )
    (comp (ref "C57")
      (value "1u")
      (footprint "eagle-import:.0603-C-NOSILK")
      (libsource (lib "eagle-import") (part "C-EU0603-C-NOSILK"))
    )
    (comp (ref "C58")
      (value "8.2p")
      (footprint "eagle-import:.0402-C-NOSILK")
      (libsource (lib "eagle-import") (part "C-EU0402-C-NOSILK"))
    )
    (comp (ref "C59")
      (value "8.2p")
      (footprint "eagle-import:.0402-C-NOSILK")
      (libsource (lib "eagle-import") (part "C-EU0402-C-NOSILK"))
    )
    (comp (ref "C60")
      (value "1n")
      (footprint "eagle-import:.0402-C-NOSILK")
      (libsource (lib "eagle-import") (part "C-EU0402-C-NOSILK"))
    )
    (comp (ref "C61")
      (value "1n")
      (footprint "eagle-import:.0402-C-NOSILK")
      (libsource (lib "eagle-import") (part "C-EU0402-C-NOSILK"))
    )
    (comp (ref "C62")
      (value "82p")
      (footprint "eagle-import:.0402-C-NOSILK")
      (libsource (lib "eagle-import") (part "C-EU0402-C-NOSILK"))
    )
    (comp (ref "C63")
      (value "82p")
      (footprint "eagle-import:.0402-C-NOSILK")
      (libsource (lib "eagle-import") (part "C-EU0402-C-NOSILK"))
    )
    (comp (ref "C64")
      (value "22p")
      (footprint "eagle-import:.0402-C-NOSILK")
      (libsource (lib "eagle-import") (part "C-EU0402-C-NOSILK"))
    )
    (comp (ref "C65")
      (value "22p")
      (footprint "eagle-import:.0402-C-NOSILK")
      (libsource (lib "eagle-import") (part "C-EU0402-C-NOSILK"))
    )
    (comp (ref "C66")
      (value "22n")
      (footprint "eagle-import:.0603-C-NOSILK")
      (libsource (lib "eagle-import") (part "C-EU0603-C-NOSILK"))
    )
    (comp (ref "C67")
      (value "NP")
      (footprint "eagle-import:.0603-C-NOSILK")
      (libsource (lib "eagle-import") (part "C-EU0603-C-NOSILK"))
    )
    (comp (ref "C68")
      (value "4.7u")
      (footprint "eagle-import:.0603-C-NOSILK")
      (libsource (lib "eagle-import") (part "C-EU0603-C-NOSILK"))
    )
    (comp (ref "C69")
      (value "22n")
      (footprint "eagle-import:.0603-C-NOSILK")
      (libsource (lib "eagle-import") (part "C-EU0603-C-NOSILK"))
    )
    (comp (ref "C70")
      (value "NP")
      (footprint "eagle-import:.0603-C-NOSILK")
      (libsource (lib "eagle-import") (part "C-EU0603-C-NOSILK"))
    )
    (comp (ref "C71")
      (value "4.7u")
      (footprint "eagle-import:.0603-C-NOSILK")
      (libsource (lib "eagle-import") (part "C-EU0603-C-NOSILK"))
    )
    (comp (ref "C72")
      (value "10n")
      (footprint "eagle-import:.0603-C-NOSILK")
      (libsource (lib "eagle-import") (part "C-EU0603-C-NOSILK"))
    )
    (comp (ref "C73")
      (value "1u")
      (footprint "eagle-import:.0603-C-NOSILK")
      (libsource (lib "eagle-import") (part "C-EU0603-C-NOSILK"))
    )
    (comp (ref "J8")
      (value "U.FL")
      (footprint "eagle-import:U.FL")
      (libsource (lib "eagle-import") (part "U.FL2PIN"))
    )
    (comp (ref "J9")
      (value "U.FL")
      (footprint "eagle-import:U.FL")
      (libsource (lib "eagle-import") (part "U.FL2PIN"))
    )
    (comp (ref "J10")
      (value "U.FL")
      (footprint "eagle-import:U.FL")
      (libsource (lib "eagle-import") (part "U.FL2PIN"))
    )
    (comp (ref "J11")
      (value "U.FL")
      (footprint "eagle-import:U.FL")
      (libsource (lib "eagle-import") (part "U.FL2PIN"))
    )
    (comp (ref "J13")
      (value "U.FL")
      (footprint "eagle-import:U.FL")
      (libsource (lib "eagle-import") (part "U.FL2PIN"))
    )
    (comp (ref "J14")
      (value "U.FL")
      (footprint "eagle-import:U.FL")
      (libsource (lib "eagle-import") (part "U.FL2PIN"))
    )
    (comp (ref "J15")
      (value "HARWIN-2X8X1.27")
      (footprint "eagle-import:2X8X1.27")
      (libsource (lib "eagle-import") (part "HARWIN-2X8X1.27"))
    )
    (comp (ref "J19")
      (value "HARWIN-2X8X1.27")
      (footprint "eagle-import:2X8X1.27")
      (libsource (lib "eagle-import") (part "HARWIN-2X8X1.27"))
    )
    (comp (ref "L6")
      (value "43n")
      (footprint "eagle-import:.0402-C-NOSILK")
      (libsource (lib "eagle-import") (part "L-US0402-C-NOSILK"))
    )
    (comp (ref "L7")
      (value "43n")
      (footprint "eagle-import:.0402-C-NOSILK")
      (libsource (lib "eagle-import") (part "L-US0402-C-NOSILK"))
    )
    (comp (ref "L8")
      (value "91n")
      (footprint "eagle-import:.0603-C-NOSILK")
      (libsource (lib "eagle-import") (part "L-US0603-C-NOSILK"))
    )
    (comp (ref "L9")
      (value "91n")
      (footprint "eagle-import:.0603-C-NOSILK")
      (libsource (lib "eagle-import") (part "L-US0603-C-NOSILK"))
    )
    (comp (ref "L10")
      (value "43n")
      (footprint "eagle-import:.0402-C-NOSILK")
      (libsource (lib "eagle-import") (part "L-US0402-C-NOSILK"))
    )
    (comp (ref "L11")
      (value "43n")
      (footprint "eagle-import:.0402-C-NOSILK")
      (libsource (lib "eagle-import") (part "L-US0402-C-NOSILK"))
    )
    (comp (ref "L12")
      (value "91n")
      (footprint "eagle-import:.0603-C-NOSILK")
      (libsource (lib "eagle-import") (part "L-US0603-C-NOSILK"))
    )
    (comp (ref "L13")
      (value "91n")
      (footprint "eagle-import:.0603-C-NOSILK")
      (libsource (lib "eagle-import") (part "L-US0603-C-NOSILK"))
    )
    (comp (ref "R28")
      (value "150")
      (footprint "eagle-import:.0402-C-NOSILK")
      (libsource (lib "eagle-import") (part "R-US_0402-C-NOSILK"))
    )
    (comp (ref "R32")
      (value "0")
      (footprint "eagle-import:.0603-C-NOSILK")
      (libsource (lib "eagle-import") (part "R-US_0603-C-NOSILK"))
    )
    (comp (ref "R33")
      (value "0")
      (footprint "eagle-import:.0603-C-NOSILK")
      (libsource (lib "eagle-import") (part "R-US_0603-C-NOSILK"))
    )
    (comp (ref "R34")
      (value "150")
      (footprint "eagle-import:.0402-C-NOSILK")
      (libsource (lib "eagle-import") (part "R-US_0402-C-NOSILK"))
    )
    (comp (ref "R39")
      (value "0")
      (footprint "eagle-import:.0603-C-NOSILK")
      (libsource (lib "eagle-import") (part "R-US_0603-C-NOSILK"))
    )
    (comp (ref "R40")
      (value "0")
      (footprint "eagle-import:.0603-C-NOSILK")
      (libsource (lib "eagle-import") (part "R-US_0603-C-NOSILK"))
    )
    (comp (ref "U11")
      (value "U-ONSEMI-AX5043")
      (footprint "eagle-import:QFN28-5X5-WITH-CENTER-PAD")
      (libsource (lib "eagle-import") (part "U-ONSEMI-AX5043"))
    )
    (comp (ref "U12")
      (value "LP2985XX-N")
      (footprint "eagle-import:SOT-23")
      (libsource (lib "eagle-import") (part "LP2985XX-N"))
    )
    (comp (ref "U13")
      (value "U-ONSEMI-AX5043")
      (footprint "eagle-import:QFN28-5X5-WITH-CENTER-PAD")
      (libsource (lib "eagle-import") (part "U-ONSEMI-AX5043"))
    )
    (comp (ref "U14")
      (value "LP2985XX-N")
      (footprint "eagle-import:SOT-23")
      (libsource (lib "eagle-import") (part "LP2985XX-N"))
    )
    (comp (ref "X3")
      (value "TAITIEN-TY")
      (footprint "eagle-import:2.5X2.0")
      (libsource (lib "eagle-import") (part "TAITIEN-TY"))
    )
    (comp (ref "X4")
      (value "TAITIEN-TY")
      (footprint "eagle-import:2.5X2.0")
      (libsource (lib "eagle-import") (part "TAITIEN-TY"))
    )
  )
  (nets
    (net (code "1") (name "3.3V") (class "Default")
      (node (ref "C12") (pin "1") (pinfunction "1_1") (pintype "passive"))
      (node (ref "C13") (pin "2") (pinfunction "2_2") (pintype "passive"))
      (node (ref "C17") (pin "2") (pinfunction "2_2") (pintype "passive"))
      (node (ref "C2") (pin "2") (pinfunction "2_2") (pintype "passive"))
      (node (ref "C22") (pin "2") (pinfunction "2_2") (pintype "passive"))
      (node (ref "C3") (pin "2") (pinfunction "2_2") (pintype "passive"))
      (node (ref "C6") (pin "2") (pinfunction "2_2") (pintype "passive"))
      (node (ref "C8") (pin "2") (pinfunction "2_2") (pintype "passive"))
      (node (ref "C9") (pin "2") (pinfunction "2_2") (pintype "passive"))
      (node (ref "D7") (pin "2") (pinfunction "A_2") (pintype "passive"))
      (node (ref "J7") (pin "1") (pinfunction "VTREF_1") (pintype "passive"))
      (node (ref "JP6") (pin "1") (pinfunction "1_1") (pintype "passive"))
      (node (ref "JP6") (pin "2") (pinfunction "2_2") (pintype "passive"))
      (node (ref "L2") (pin "2") (pinfunction "2_2") (pintype "passive"))
      (node (ref "Q1") (pin "4") (pinfunction "S_4") (pintype "passive"))
      (node (ref "R12") (pin "2") (pinfunction "2_2") (pintype "passive"))
      (node (ref "R13") (pin "1") (pinfunction "1_1") (pintype "passive"))
      (node (ref "R14") (pin "10") (pinfunction "55_10") (pintype "passive"))
      (node (ref "R14") (pin "5") (pinfunction "55_5") (pintype "passive"))
      (node (ref "R15") (pin "10") (pinfunction "55_10") (pintype "passive"))
      (node (ref "R15") (pin "5") (pinfunction "55_5") (pintype "passive"))
      (node (ref "R16") (pin "2") (pinfunction "2_2") (pintype "passive"))
      (node (ref "R2") (pin "2") (pinfunction "2_2") (pintype "passive"))
      (node (ref "R27") (pin "2") (pinfunction "2_2") (pintype "passive"))
      (node (ref "R32") (pin "1") (pinfunction "1_1") (pintype "passive"))
      (node (ref "R33") (pin "2") (pinfunction "2_2") (pintype "passive"))
      (node (ref "R39") (pin "1") (pinfunction "1_1") (pintype "passive"))
      (node (ref "R40") (pin "2") (pinfunction "2_2") (pintype "passive"))
      (node (ref "TP17") (pin "1") (pinfunction "1_1") (pintype "passive"))
      (node (ref "TP9") (pin "1") (pinfunction "1_1") (pintype "passive"))
      (node (ref "U2") (pin "3") (pinfunction "VCC_3") (pintype "power_in"))
      (node (ref "U3") (pin "3") (pinfunction "VCC_3") (pintype "power_in"))
      (node (ref "U5") (pin "10") (pinfunction "FB_10") (pintype "input"))
      (node (ref "U7") (pin "1") (pinfunction "VBAT_1") (pintype "power_in"))
      (node (ref "U7") (pin "13") (pinfunction "VDDA_13") (pintype "power_in"))
      (node (ref "U7") (pin "19") (pinfunction "VDD_19") (pintype "power_in"))
      (node (ref "U7") (pin "32") (pinfunction "VDD_32") (pintype "power_in"))
      (node (ref "U7") (pin "48") (pinfunction "VDD_48") (pintype "power_in"))
      (node (ref "U7") (pin "64") (pinfunction "VDD_64") (pintype "power_in"))
    )
    (net (code "2") (name "AUX-1") (class "Default")
      (node (ref "J1") (pin "1") (pinfunction "1_1") (pintype "passive"))
      (node (ref "J1") (pin "2") (pinfunction "2_2") (pintype "passive"))
      (node (ref "JP9") (pin "1") (pinfunction "1_1") (pintype "passive"))
    )
    (net (code "3") (name "AUX-2") (class "Default")
      (node (ref "J1") (pin "3") (pinfunction "3_3") (pintype "passive"))
      (node (ref "J1") (pin "4") (pinfunction "4_4") (pintype "passive"))
      (node (ref "JP9") (pin "2") (pinfunction "2_2") (pintype "passive"))
    )
    (net (code "4") (name "AUX-3") (class "Default")
      (node (ref "J1") (pin "5") (pinfunction "5_5") (pintype "passive"))
      (node (ref "J1") (pin "6") (pinfunction "6_6") (pintype "passive"))
      (node (ref "JP9") (pin "3") (pinfunction "3_3") (pintype "passive"))
    )
    (net (code "5") (name "AUX-4") (class "Default")
      (node (ref "J1") (pin "7") (pinfunction "7_7") (pintype "passive"))
      (node (ref "J1") (pin "8") (pinfunction "8_8") (pintype "passive"))
      (node (ref "JP9") (pin "4") (pinfunction "4_4") (pintype "passive"))
    )
    (net (code "6") (name "AUX-5") (class "Default")
      (node (ref "J1") (pin "10") (pinfunction "10_10") (pintype "passive"))
      (node (ref "J1") (pin "9") (pinfunction "9_9") (pintype "passive"))
      (node (ref "JP9") (pin "5") (pinfunction "5_5") (pintype "passive"))
    )
    (net (code "7") (name "AUX-6") (class "Default")
      (node (ref "J1") (pin "11") (pinfunction "11_11") (pintype "passive"))
      (node (ref "J1") (pin "12") (pinfunction "12_12") (pintype "passive"))
      (node (ref "JP9") (pin "6") (pinfunction "6_6") (pintype "passive"))
    )
    (net (code "8") (name "AUX-7") (class "Default")
      (node (ref "J1") (pin "13") (pinfunction "13_13") (pintype "passive"))
      (node (ref "J1") (pin "14") (pinfunction "14_14") (pintype "passive"))
      (node (ref "JP9") (pin "7") (pinfunction "7_7") (pintype "passive"))
    )
    (net (code "9") (name "AUX-8") (class "Default")
      (node (ref "J1") (pin "15") (pinfunction "15_15") (pintype "passive"))
      (node (ref "J1") (pin "16") (pinfunction "16_16") (pintype "passive"))
      (node (ref "JP9") (pin "8") (pinfunction "8_8") (pintype "passive"))
    )
    (net (code "10") (name "AUX-9") (class "Default")
      (node (ref "J1") (pin "17") (pinfunction "17_17") (pintype "passive"))
      (node (ref "J1") (pin "18") (pinfunction "18_18") (pintype "passive"))
      (node (ref "JP9") (pin "9") (pinfunction "9_9") (pintype "passive"))
    )
    (net (code "11") (name "AUX_~{SHUTDOWN}") (class "Default")
      (node (ref "J1") (pin "19") (pinfunction "19_19") (pintype "passive"))
      (node (ref "J1") (pin "20") (pinfunction "20_20") (pintype "passive"))
      (node (ref "JP9") (pin "10") (pinfunction "10_10") (pintype "passive"))
    )
    (net (code "12") (name "CAN1_H") (class "Default")
      (node (ref "J6") (pin "33") (pinfunction "33_33") (pintype "passive"))
      (node (ref "J6") (pin "34") (pinfunction "34_34") (pintype "passive"))
      (node (ref "JP10") (pin "5") (pinfunction "5_5") (pintype "passive"))
      (node (ref "JP10") (pin "6") (pinfunction "6_6") (pintype "passive"))
      (node (ref "U2") (pin "7") (pinfunction "CANH_7") (pintype "bidirectional"))
    )
    (net (code "13") (name "CAN1_L") (class "Default")
      (node (ref "J6") (pin "35") (pinfunction "35_35") (pintype "passive"))
      (node (ref "J6") (pin "36") (pinfunction "36_36") (pintype "passive"))
      (node (ref "JP10") (pin "7") (pinfunction "7_7") (pintype "passive"))
      (node (ref "JP10") (pin "8") (pinfunction "8_8") (pintype "passive"))
      (node (ref "U2") (pin "6") (pinfunction "CANL_6") (pintype "bidirectional"))
    )
    (net (code "14") (name "CAN1_RX") (class "Default")
      (node (ref "U2") (pin "4") (pinfunction "RXD_4") (pintype "output"))
      (node (ref "U7") (pin "44") (pinfunction "PA11_44") (pintype "bidirectional"))
    )
    (net (code "15") (name "CAN1_SHDN") (class "Default")
      (node (ref "U2") (pin "5") (pinfunction "SHDN_5") (pintype "input"))
      (node (ref "U7") (pin "43") (pinfunction "PA10_43") (pintype "bidirectional"))
    )
    (net (code "16") (name "CAN1_SILENT") (class "Default")
      (node (ref "U2") (pin "8") (pinfunction "S_8") (pintype "input"))
      (node (ref "U7") (pin "42") (pinfunction "PA9_42") (pintype "bidirectional"))
    )
    (net (code "17") (name "CAN1_TX") (class "Default")
      (node (ref "U2") (pin "1") (pinfunction "TXD_1") (pintype "input"))
      (node (ref "U7") (pin "45") (pinfunction "PA12_45") (pintype "bidirectional"))
    )
    (net (code "18") (name "CAN2_H") (class "Default")
      (node (ref "J6") (pin "17") (pinfunction "17_17") (pintype "passive"))
      (node (ref "J6") (pin "18") (pinfunction "18_18") (pintype "passive"))
      (node (ref "JP1") (pin "7") (pinfunction "7_7") (pintype "passive"))
      (node (ref "JP1") (pin "8") (pinfunction "8_8") (pintype "passive"))
      (node (ref "U3") (pin "7") (pinfunction "CANH_7") (pintype "bidirectional"))
    )
    (net (code "19") (name "CAN2_L") (class "Default")
      (node (ref "J6") (pin "19") (pinfunction "19_19") (pintype "passive"))
      (node (ref "J6") (pin "20") (pinfunction "20_20") (pintype "passive"))
      (node (ref "JP1") (pin "10") (pinfunction "10_10") (pintype "passive"))
      (node (ref "JP1") (pin "9") (pinfunction "9_9") (pintype "passive"))
      (node (ref "U3") (pin "6") (pinfunction "CANL_6") (pintype "bidirectional"))
    )
    (net (code "20") (name "CAN2_RX") (class "Default")
      (node (ref "U3") (pin "4") (pinfunction "RXD_4") (pintype "output"))
      (node (ref "U7") (pin "57") (pinfunction "PB5_57") (pintype "bidirectional"))
    )
    (net (code "21") (name "CAN2_SHDN") (class "Default")
      (node (ref "U3") (pin "5") (pinfunction "SHDN_5") (pintype "input"))
      (node (ref "U7") (pin "56") (pinfunction "PB4_56") (pintype "bidirectional"))
    )
    (net (code "22") (name "CAN2_SILENT") (class "Default")
      (node (ref "U3") (pin "8") (pinfunction "S_8") (pintype "input"))
      (node (ref "U7") (pin "59") (pinfunction "PB7_59") (pintype "bidirectional"))
    )
    (net (code "23") (name "CAN2_TX") (class "Default")
      (node (ref "U3") (pin "1") (pinfunction "TXD_1") (pintype "input"))
      (node (ref "U7") (pin "58") (pinfunction "PB6_58") (pintype "bidirectional"))
    )
    (net (code "24") (name "CB_IOUT") (class "Default")
      (node (ref "R20") (pin "1") (pinfunction "1_1") (pintype "passive"))
      (node (ref "R6") (pin "2") (pinfunction "2_2") (pintype "passive"))
      (node (ref "TP10") (pin "1") (pinfunction "1_1") (pintype "passive"))
      (node (ref "U4") (pin "7") (pinfunction "ILIM_7") (pintype "bidirectional"))
    )
    (net (code "25") (name "CB_IOUT_IN") (class "Default")
      (node (ref "R20") (pin "2") (pinfunction "2_2") (pintype "passive"))
      (node (ref "U7") (pin "26") (pinfunction "PB0_26") (pintype "bidirectional"))
    )
    (net (code "26") (name "GND") (class "Default")
      (node (ref "C1") (pin "2") (pinfunction "2_2") (pintype "passive"))
      (node (ref "C10") (pin "2") (pinfunction "2_2") (pintype "passive"))
      (node (ref "C11") (pin "2") (pinfunction "2_2") (pintype "passive"))
      (node (ref "C12") (pin "2") (pinfunction "2_2") (pintype "passive"))
      (node (ref "C13") (pin "1") (pinfunction "1_1") (pintype "passive"))
      (node (ref "C14") (pin "2") (pinfunction "2_2") (pintype "passive"))
      (node (ref "C15") (pin "2") (pinfunction "2_2") (pintype "passive"))
      (node (ref "C16") (pin "2") (pinfunction "2_2") (pintype "passive"))
      (node (ref "C17") (pin "1") (pinfunction "1_1") (pintype "passive"))
      (node (ref "C18") (pin "2") (pinfunction "2_2") (pintype "passive"))
      (node (ref "C19") (pin "2") (pinfunction "2_2") (pintype "passive"))
      (node (ref "C2") (pin "1") (pinfunction "1_1") (pintype "passive"))
      (node (ref "C21") (pin "2") (pinfunction "2_2") (pintype "passive"))
      (node (ref "C22") (pin "1") (pinfunction "1_1") (pintype "passive"))
      (node (ref "C23") (pin "2") (pinfunction "2_2") (pintype "passive"))
      (node (ref "C24") (pin "2") (pinfunction "2_2") (pintype "passive"))
      (node (ref "C25") (pin "2") (pinfunction "2_2") (pintype "passive"))
      (node (ref "C26") (pin "2") (pinfunction "2_2") (pintype "passive"))
      (node (ref "C3") (pin "1") (pinfunction "1_1") (pintype "passive"))
      (node (ref "C4") (pin "2") (pinfunction "2_2") (pintype "passive"))
      (node (ref "C43") (pin "1") (pinfunction "1_1") (pintype "passive"))
      (node (ref "C44") (pin "2") (pinfunction "2_2") (pintype "passive"))
      (node (ref "C46") (pin "2") (pinfunction "2_2") (pintype "passive"))
      (node (ref "C47") (pin "1") (pinfunction "1_1") (pintype "passive"))
      (node (ref "C5") (pin "2") (pinfunction "2_2") (pintype "passive"))
      (node (ref "C50") (pin "2") (pinfunction "2_2") (pintype "passive"))
      (node (ref "C51") (pin "2") (pinfunction "2_2") (pintype "passive"))
      (node (ref "C52") (pin "2") (pinfunction "2_2") (pintype "passive"))
      (node (ref "C53") (pin "2") (pinfunction "2_2") (pintype "passive"))
      (node (ref "C54") (pin "2") (pinfunction "2_2") (pintype "passive"))
      (node (ref "C55") (pin "2") (pinfunction "2_2") (pintype "passive"))
      (node (ref "C56") (pin "2") (pinfunction "2_2") (pintype "passive"))
      (node (ref "C57") (pin "2") (pinfunction "2_2") (pintype "passive"))
      (node (ref "C59") (pin "1") (pinfunction "1_1") (pintype "passive"))
      (node (ref "C6") (pin "1") (pinfunction "1_1") (pintype "passive"))
      (node (ref "C60") (pin "2") (pinfunction "2_2") (pintype "passive"))
      (node (ref "C62") (pin "2") (pinfunction "2_2") (pintype "passive"))
      (node (ref "C63") (pin "1") (pinfunction "1_1") (pintype "passive"))
      (node (ref "C66") (pin "2") (pinfunction "2_2") (pintype "passive"))
      (node (ref "C67") (pin "2") (pinfunction "2_2") (pintype "passive"))
      (node (ref "C68") (pin "2") (pinfunction "2_2") (pintype "passive"))
      (node (ref "C69") (pin "2") (pinfunction "2_2") (pintype "passive"))
      (node (ref "C7") (pin "2") (pinfunction "2_2") (pintype "passive"))
      (node (ref "C70") (pin "2") (pinfunction "2_2") (pintype "passive"))
      (node (ref "C71") (pin "2") (pinfunction "2_2") (pintype "passive"))
      (node (ref "C72") (pin "2") (pinfunction "2_2") (pintype "passive"))
      (node (ref "C73") (pin "2") (pinfunction "2_2") (pintype "passive"))
      (node (ref "C8") (pin "1") (pinfunction "1_1") (pintype "passive"))
      (node (ref "C9") (pin "1") (pinfunction "1_1") (pintype "passive"))
      (node (ref "CM1") (pin "P$1") (pinfunction "SHIELD3_P$1") (pintype "passive"))
      (node (ref "CM1") (pin "P$2") (pinfunction "SHIELD2_P$2") (pintype "passive"))
      (node (ref "CM1") (pin "P$3") (pinfunction "SHIELD1_P$3") (pintype "passive"))
      (node (ref "CM1") (pin "P$4") (pinfunction "SHIELD_P$4") (pintype "passive"))
      (node (ref "CM2") (pin "P$1") (pinfunction "SHIELD3_P$1") (pintype "passive"))
      (node (ref "CM2") (pin "P$2") (pinfunction "SHIELD2_P$2") (pintype "passive"))
      (node (ref "CM2") (pin "P$3") (pinfunction "SHIELD1_P$3") (pintype "passive"))
      (node (ref "CM2") (pin "P$4") (pinfunction "SHIELD_P$4") (pintype "passive"))
      (node (ref "CM3") (pin "P$1") (pinfunction "SHIELD3_P$1") (pintype "passive"))
      (node (ref "CM3") (pin "P$2") (pinfunction "SHIELD2_P$2") (pintype "passive"))
      (node (ref "CM3") (pin "P$3") (pinfunction "SHIELD1_P$3") (pintype "passive"))
      (node (ref "CM3") (pin "P$4") (pinfunction "SHIELD_P$4") (pintype "passive"))
      (node (ref "D1") (pin "C") (pinfunction "C_C") (pintype "passive"))
      (node (ref "D2") (pin "C") (pinfunction "C_C") (pintype "passive"))
      (node (ref "D3") (pin "C") (pinfunction "C_C") (pintype "passive"))
      (node (ref "D5") (pin "C") (pinfunction "C_C") (pintype "passive"))
      (node (ref "J10") (pin "1") (pinfunction "GND_1") (pintype "bidirectional"))
      (node (ref "J10") (pin "2") (pinfunction "GND_2") (pintype "bidirectional"))
      (node (ref "J11") (pin "1") (pinfunction "GND_1") (pintype "bidirectional"))
      (node (ref "J11") (pin "2") (pinfunction "GND_2") (pintype "bidirectional"))
      (node (ref "J13") (pin "1") (pinfunction "GND_1") (pintype "bidirectional"))
      (node (ref "J13") (pin "2") (pinfunction "GND_2") (pintype "bidirectional"))
      (node (ref "J14") (pin "1") (pinfunction "GND_1") (pintype "bidirectional"))
      (node (ref "J14") (pin "2") (pinfunction "GND_2") (pintype "bidirectional"))
      (node (ref "J15") (pin "13") (pinfunction "13_13") (pintype "passive"))
      (node (ref "J15") (pin "14") (pinfunction "14_14") (pintype "passive"))
      (node (ref "J15") (pin "15") (pinfunction "15_15") (pintype "passive"))
      (node (ref "J15") (pin "16") (pinfunction "16_16") (pintype "passive"))
      (node (ref "J19") (pin "13") (pinfunction "13_13") (pintype "passive"))
      (node (ref "J19") (pin "14") (pinfunction "14_14") (pintype "passive"))
      (node (ref "J19") (pin "15") (pinfunction "15_15") (pintype "passive"))
      (node (ref "J19") (pin "16") (pinfunction "16_16") (pintype "passive"))
      (node (ref "J2") (pin "1") (pinfunction "GND_1") (pintype "bidirectional"))
      (node (ref "J2") (pin "2") (pinfunction "GND_2") (pintype "bidirectional"))
      (node (ref "J3") (pin "1") (pinfunction "GND_1") (pintype "bidirectional"))
      (node (ref "J3") (pin "2") (pinfunction "GND_2") (pintype "bidirectional"))
      (node (ref "J4") (pin "1") (pinfunction "GND_1") (pintype "bidirectional"))
      (node (ref "J4") (pin "2") (pinfunction "GND_2") (pintype "bidirectional"))
      (node (ref "J5") (pin "P$6") (pinfunction "GND_P$6") (pintype "passive"))
      (node (ref "J6") (pin "27") (pinfunction "27_27") (pintype "passive"))
      (node (ref "J6") (pin "28") (pinfunction "28_28") (pintype "passive"))
      (node (ref "J6") (pin "29") (pinfunction "29_29") (pintype "passive"))
      (node (ref "J6") (pin "30") (pinfunction "30_30") (pintype "passive"))
      (node (ref "J6") (pin "31") (pinfunction "31_31") (pintype "passive"))
      (node (ref "J6") (pin "32") (pinfunction "32_32") (pintype "passive"))
      (node (ref "J6") (pin "37") (pinfunction "37_37") (pintype "passive"))
      (node (ref "J6") (pin "38") (pinfunction "38_38") (pintype "passive"))
      (node (ref "J7") (pin "3") (pinfunction "GND_3") (pintype "passive"))
      (node (ref "J7") (pin "5") (pinfunction "GND_5") (pintype "passive"))
      (node (ref "J7") (pin "9") (pinfunction "GNDDET_9") (pintype "passive"))
      (node (ref "J8") (pin "1") (pinfunction "GND_1") (pintype "bidirectional"))
      (node (ref "J8") (pin "2") (pinfunction "GND_2") (pintype "bidirectional"))
      (node (ref "J9") (pin "1") (pinfunction "GND_1") (pintype "bidirectional"))
      (node (ref "J9") (pin "2") (pinfunction "GND_2") (pintype "bidirectional"))
      (node (ref "JP2") (pin "10") (pinfunction "10_10") (pintype "passive"))
      (node (ref "JP2") (pin "7") (pinfunction "7_7") (pintype "passive"))
      (node (ref "JP2") (pin "8") (pinfunction "8_8") (pintype "passive"))
      (node (ref "JP2") (pin "9") (pinfunction "9_9") (pintype "passive"))
      (node (ref "L11") (pin "1") (pinfunction "1_1") (pintype "passive"))
      (node (ref "L12") (pin "2") (pinfunction "2_2") (pintype "passive"))
      (node (ref "L13") (pin "1") (pinfunction "1_1") (pintype "passive"))
      (node (ref "L7") (pin "1") (pinfunction "1_1") (pintype "passive"))
      (node (ref "L8") (pin "2") (pinfunction "2_2") (pintype "passive"))
      (node (ref "L9") (pin "1") (pinfunction "1_1") (pintype "passive"))
      (node (ref "R10") (pin "1") (pinfunction "1_1") (pintype "passive"))
      (node (ref "R17") (pin "1") (pinfunction "1_1") (pintype "passive"))
      (node (ref "R36") (pin "1") (pinfunction "1_1") (pintype "passive"))
      (node (ref "R6") (pin "1") (pinfunction "1_1") (pintype "passive"))
      (node (ref "R9") (pin "1") (pinfunction "1_1") (pintype "passive"))
      (node (ref "TP11") (pin "1") (pinfunction "1_1") (pintype "passive"))
      (node (ref "U1") (pin "4") (pinfunction "GND_4") (pintype "power_in"))
      (node (ref "U11") (pin "2") (pinfunction "GND1_2") (pintype "power_in"))
      (node (ref "U11") (pin "25") (pinfunction "GPADC1_25") (pintype "input"))
      (node (ref "U11") (pin "26") (pinfunction "GPADC2_26") (pintype "input"))
      (node (ref "U11") (pin "6") (pinfunction "GND2_6") (pintype "power_in"))
      (node (ref "U11") (pin "PAD") (pinfunction "PGND_PAD") (pintype "power_in"))
      (node (ref "U12") (pin "2") (pinfunction "GND_2") (pintype "power_in"))
      (node (ref "U13") (pin "2") (pinfunction "GND1_2") (pintype "power_in"))
      (node (ref "U13") (pin "25") (pinfunction "GPADC1_25") (pintype "input"))
      (node (ref "U13") (pin "26") (pinfunction "GPADC2_26") (pintype "input"))
      (node (ref "U13") (pin "6") (pinfunction "GND2_6") (pintype "power_in"))
      (node (ref "U13") (pin "PAD") (pinfunction "PGND_PAD") (pintype "power_in"))
      (node (ref "U14") (pin "2") (pinfunction "GND_2") (pintype "power_in"))
      (node (ref "U2") (pin "2") (pinfunction "GND_2") (pintype "power_in"))
      (node (ref "U3") (pin "2") (pinfunction "GND_2") (pintype "power_in"))
      (node (ref "U4") (pin "1") (pinfunction "GND_1") (pintype "bidirectional"))
      (node (ref "U4") (pin "THERMAL") (pinfunction "GND_THERMAL") (pintype "bidirectional"))
      (node (ref "U5") (pin "1") (pinfunction "GND_1") (pintype "power_in"))
      (node (ref "U5") (pin "11") (pinfunction "GND_11") (pintype "power_in"))
      (node (ref "U5") (pin "12") (pinfunction "GND_12") (pintype "power_in"))
      (node (ref "U5") (pin "16") (pinfunction "GND_16") (pintype "power_in"))
      (node (ref "U5") (pin "6") (pinfunction "LBO_6") (pintype "open_collector"))
      (node (ref "U5") (pin "7") (pinfunction "LBI_7") (pintype "input"))
      (node (ref "U5") (pin "9") (pinfunction "GND_9") (pintype "power_in"))
      (node (ref "U5") (pin "PAD") (pinfunction "GND_PAD") (pintype "power_in"))
      (node (ref "U6") (pin "2") (pinfunction "GND_2") (pintype "power_in"))
      (node (ref "U6") (pin "5") (pinfunction "SET1_5") (pintype "input"))
      (node (ref "U6") (pin "6") (pinfunction "SET2_6") (pintype "input"))
      (node (ref "U7") (pin "12") (pinfunction "VSSA_12") (pintype "power_in"))
      (node (ref "U7") (pin "18") (pinfunction "VSS_18") (pintype "power_in"))
      (node (ref "U7") (pin "31") (pinfunction "VSS_31") (pintype "power_in"))
      (node (ref "U7") (pin "47") (pinfunction "VSS_47") (pintype "power_in"))
      (node (ref "U7") (pin "63") (pinfunction "VSS_63") (pintype "power_in"))
      (node (ref "U9") (pin "A6") (pinfunction "VSSIO_A6") (pintype "power_in"))
      (node (ref "U9") (pin "C4") (pinfunction "VSSQ_C4") (pintype "power_in"))
      (node (ref "U9") (pin "D4") (pinfunction "VSSIO_D4") (pintype "power_in"))
      (node (ref "U9") (pin "E7") (pinfunction "VSSIO_E7") (pintype "power_in"))
      (node (ref "U9") (pin "G5") (pinfunction "VSSIO_G5") (pintype "power_in"))
      (node (ref "U9") (pin "H10") (pinfunction "VSSIO_H10") (pintype "power_in"))
      (node (ref "U9") (pin "J5") (pinfunction "VSSIO_J5") (pintype "power_in"))
      (node (ref "U9") (pin "K8") (pinfunction "VSSIO_K8") (pintype "power_in"))
      (node (ref "U9") (pin "N1") (pinfunction "VSSQ_N1") (pintype "power_in"))
      (node (ref "U9") (pin "N2") (pinfunction "VSSQ_N2") (pintype "power_in"))
      (node (ref "U9") (pin "N5") (pinfunction "VSSQ_N5") (pintype "power_in"))
      (node (ref "U9") (pin "P4") (pinfunction "VSSQ_P4") (pintype "power_in"))
      (node (ref "U9") (pin "P6") (pinfunction "VSSQ_P6") (pintype "power_in"))
      (node (ref "X1") (pin "2") (pinfunction "SHIELD_2") (pintype "power_in"))
      (node (ref "X1") (pin "4") (pinfunction "SHIELD_4") (pintype "power_in"))
      (node (ref "X3") (pin "2") (pinfunction "GND_2") (pintype "power_in"))
      (node (ref "X4") (pin "2") (pinfunction "GND_2") (pintype "power_in"))
    )
    (net (code "27") (name "MMC_PWR") (class "Default")
      (node (ref "Q1") (pin "3") (pinfunction "G_3") (pintype "passive"))
      (node (ref "R14") (pin "1") (pinfunction "11_1") (pintype "passive"))
      (node (ref "U7") (pin "2") (pinfunction "PC13_2") (pintype "bidirectional"))
    )
    (net (code "28") (name "MMC_VDD") (class "Default")
      (node (ref "C23") (pin "1") (pinfunction "1_1") (pintype "passive"))
      (node (ref "C24") (pin "1") (pinfunction "1_1") (pintype "passive"))
      (node (ref "C25") (pin "1") (pinfunction "1_1") (pintype "passive"))
      (node (ref "C26") (pin "1") (pinfunction "1_1") (pintype "passive"))
      (node (ref "Q1") (pin "1") (pinfunction "D_1") (pintype "passive"))
      (node (ref "Q1") (pin "2") (pinfunction "D_2") (pintype "passive"))
      (node (ref "Q1") (pin "5") (pinfunction "D_5") (pintype "passive"))
      (node (ref "Q1") (pin "6") (pinfunction "D_6") (pintype "passive"))
      (node (ref "U9") (pin "C6") (pinfunction "VDDQ_C6") (pintype "power_in"))
      (node (ref "U9") (pin "E6") (pinfunction "VDDIO_E6") (pintype "power_in"))
      (node (ref "U9") (pin "F5") (pinfunction "VDDIO_F5") (pintype "power_in"))
      (node (ref "U9") (pin "J10") (pinfunction "VDDIO_J10") (pintype "power_in"))
      (node (ref "U9") (pin "K9") (pinfunction "VDDIO_K9") (pintype "power_in"))
      (node (ref "U9") (pin "M4") (pinfunction "VDDQ_M4") (pintype "power_in"))
      (node (ref "U9") (pin "N4") (pinfunction "VDDQ_N4") (pintype "power_in"))
      (node (ref "U9") (pin "P3") (pinfunction "VDDQ_P3") (pintype "power_in"))
      (node (ref "U9") (pin "P5") (pinfunction "VDDQ_P5") (pintype "power_in"))
    )
    (net (code "29") (name "NRST") (class "Default")
      (node (ref "J7") (pin "10") (pinfunction "~{RESET}_10") (pintype "passive"))
      (node (ref "TP2") (pin "1") (pinfunction "1_1") (pintype "passive"))
      (node (ref "U7") (pin "7") (pinfunction "NRST_7") (pintype "bidirectional"))
    )
    (net (code "30") (name "Net-(C42-Pad1)") (class "Default")
      (node (ref "C42") (pin "1") (pinfunction "1_1") (pintype "passive"))
      (node (ref "C48") (pin "2") (pinfunction "2_2") (pintype "passive"))
      (node (ref "L6") (pin "1") (pinfunction "1_1") (pintype "passive"))
    )
    (net (code "31") (name "Net-(C58-Pad1)") (class "Default")
      (node (ref "C58") (pin "1") (pinfunction "1_1") (pintype "passive"))
      (node (ref "C64") (pin "2") (pinfunction "2_2") (pintype "passive"))
      (node (ref "L10") (pin "1") (pinfunction "1_1") (pintype "passive"))
    )
    (net (code "32") (name "Net-(CM1-CENTER)") (class "Default")
      (node (ref "CM1") (pin "RF") (pinfunction "CENTER_RF") (pintype "passive"))
      (node (ref "J2") (pin "FEED") (pinfunction "SIGNAL_FEED") (pintype "bidirectional"))
    )
    (net (code "33") (name "Net-(CM2-CENTER)") (class "Default")
      (node (ref "CM2") (pin "RF") (pinfunction "CENTER_RF") (pintype "passive"))
      (node (ref "J3") (pin "FEED") (pinfunction "SIGNAL_FEED") (pintype "bidirectional"))
    )
    (net (code "34") (name "Net-(CM3-CENTER)") (class "Default")
      (node (ref "CM3") (pin "RF") (pinfunction "CENTER_RF") (pintype "passive"))
      (node (ref "J4") (pin "FEED") (pinfunction "SIGNAL_FEED") (pintype "bidirectional"))
    )
    (net (code "35") (name "Net-(D1-PadA)") (class "Default")
      (node (ref "D1") (pin "A") (pinfunction "A_A") (pintype "passive"))
      (node (ref "R1") (pin "1") (pinfunction "1_1") (pintype "passive"))
    )
    (net (code "36") (name "Net-(D2-PadA)") (class "Default")
      (node (ref "D2") (pin "A") (pinfunction "A_A") (pintype "passive"))
      (node (ref "R2") (pin "1") (pinfunction "1_1") (pintype "passive"))
    )
    (net (code "37") (name "Net-(D3-PadA)") (class "Default")
      (node (ref "D3") (pin "A") (pinfunction "A_A") (pintype "passive"))
      (node (ref "R3") (pin "1") (pinfunction "1_1") (pintype "passive"))
    )
    (net (code "38") (name "Net-(D4-PadA)") (class "Default")
      (node (ref "D4") (pin "A") (pinfunction "A_A") (pintype "passive"))
      (node (ref "R27") (pin "1") (pinfunction "1_1") (pintype "passive"))
    )
    (net (code "39") (name "Net-(D5-PadA)") (class "Default")
      (node (ref "D5") (pin "A") (pinfunction "A_A") (pintype "passive"))
      (node (ref "R4") (pin "1") (pinfunction "1_1") (pintype "passive"))
    )
    (net (code "40") (name "Net-(D7-C)") (class "Default")
      (node (ref "D7") (pin "1") (pinfunction "C_1") (pintype "passive"))
      (node (ref "R19") (pin "2") (pinfunction "2_2") (pintype "passive"))
    )
    (net (code "41") (name "Net-(J5-VCC)") (class "Default")
      (node (ref "J5") (pin "P$4") (pinfunction "VCC_P$4") (pintype "passive"))
      (node (ref "JP8") (pin "2") (pinfunction "2_2") (pintype "passive"))
    )
    (net (code "42") (name "Net-(J9-SIGNAL)") (class "Default")
      (node (ref "C49") (pin "1") (pinfunction "1_1") (pintype "passive"))
      (node (ref "J9") (pin "FEED") (pinfunction "SIGNAL_FEED") (pintype "bidirectional"))
    )
    (net (code "43") (name "Net-(J10-SIGNAL)") (class "Default")
      (node (ref "C48") (pin "1") (pinfunction "1_1") (pintype "passive"))
      (node (ref "J10") (pin "FEED") (pinfunction "SIGNAL_FEED") (pintype "bidirectional"))
    )
    (net (code "44") (name "Net-(J11-SIGNAL)") (class "Default")
      (node (ref "C64") (pin "1") (pinfunction "1_1") (pintype "passive"))
      (node (ref "J11") (pin "FEED") (pinfunction "SIGNAL_FEED") (pintype "bidirectional"))
    )
    (net (code "45") (name "Net-(J13-SIGNAL)") (class "Default")
      (node (ref "C65") (pin "1") (pinfunction "1_1") (pintype "passive"))
      (node (ref "J13") (pin "FEED") (pinfunction "SIGNAL_FEED") (pintype "bidirectional"))
    )
    (net (code "46") (name "Net-(J14-SIGNAL)") (class "Default")
      (node (ref "J14") (pin "FEED") (pinfunction "SIGNAL_FEED") (pintype "bidirectional"))
      (node (ref "U13") (pin "13") (pinfunction "SYSCLK_13") (pintype "bidirectional"))
    )
    (net (code "47") (name "Net-(L2-Pad1)") (class "Default")
      (node (ref "L2") (pin "1") (pinfunction "1_1") (pintype "passive"))
      (node (ref "U5") (pin "14") (pinfunction "SW_14") (pintype "output"))
      (node (ref "U5") (pin "15") (pinfunction "SW_15") (pintype "output"))
    )
    (net (code "48") (name "Net-(U1-IN)") (class "Default")
      (node (ref "C5") (pin "1") (pinfunction "1_1") (pintype "passive"))
      (node (ref "R12") (pin "1") (pinfunction "1_1") (pintype "passive"))
      (node (ref "U1") (pin "1") (pinfunction "IN_2_1") (pintype "power_in"))
      (node (ref "U1") (pin "2") (pinfunction "IN_2") (pintype "power_in"))
    )
    (net (code "49") (name "Net-(U4-EN{slash}UVLO)") (class "Default")
      (node (ref "R5") (pin "1") (pinfunction "1_1") (pintype "passive"))
      (node (ref "R9") (pin "2") (pinfunction "2_2") (pintype "passive"))
      (node (ref "U4") (pin "3") (pinfunction "EN/UVLO_3") (pintype "bidirectional"))
    )
    (net (code "50") (name "Net-(U4-~{FLT})") (class "Default")
      (node (ref "TP1") (pin "1") (pinfunction "1_1") (pintype "passive"))
      (node (ref "U4") (pin "6") (pinfunction "~{FLT}_6") (pintype "bidirectional"))
    )
    (net (code "51") (name "Net-(U5-PG)") (class "Default")
      (node (ref "TP16") (pin "1") (pinfunction "1_1") (pintype "passive"))
      (node (ref "U5") (pin "13") (pinfunction "PG_13") (pintype "open_collector"))
    )
    (net (code "52") (name "Net-(U5-SYNC)") (class "Default")
      (node (ref "R10") (pin "2") (pinfunction "2_2") (pintype "passive"))
      (node (ref "R7") (pin "1") (pinfunction "1_1") (pintype "passive"))
      (node (ref "TP19") (pin "1") (pinfunction "1_1") (pintype "passive"))
      (node (ref "U5") (pin "5") (pinfunction "SYNC_5") (pintype "input"))
    )
    (net (code "53") (name "Net-(U6-SET0)") (class "Default")
      (node (ref "C15") (pin "1") (pinfunction "1_1") (pintype "passive"))
      (node (ref "C18") (pin "1") (pinfunction "1_1") (pintype "passive"))
      (node (ref "R19") (pin "1") (pinfunction "1_1") (pintype "passive"))
      (node (ref "U6") (pin "4") (pinfunction "SET0_4") (pintype "input"))
      (node (ref "U6") (pin "8") (pinfunction "VCC_8") (pintype "power_in"))
    )
    (net (code "54") (name "Net-(U7-BOOT0)") (class "Default")
      (node (ref "R17") (pin "2") (pinfunction "2_2") (pintype "passive"))
      (node (ref "TP15") (pin "1") (pinfunction "1_1") (pintype "passive"))
      (node (ref "U7") (pin "60") (pinfunction "BOOT0_60") (pintype "bidirectional"))
    )
    (net (code "55") (name "Net-(U7-PH0-OSC_IN)") (class "Default")
      (node (ref "C16") (pin "1") (pinfunction "1_1") (pintype "passive"))
      (node (ref "U7") (pin "5") (pinfunction "PH0-OSC_IN_5") (pintype "bidirectional"))
      (node (ref "X1") (pin "1") (pinfunction "1_1") (pintype "passive"))
    )
    (net (code "56") (name "Net-(U7-PH1-OSC_OUT)") (class "Default")
      (node (ref "C11") (pin "1") (pinfunction "1_1") (pintype "passive"))
      (node (ref "U7") (pin "6") (pinfunction "PH1-OSC_OUT_6") (pintype "bidirectional"))
      (node (ref "X1") (pin "3") (pinfunction "2_3") (pintype "passive"))
    )
    (net (code "57") (name "Net-(U11-ANTN)") (class "Default")
      (node (ref "C42") (pin "2") (pinfunction "2_2") (pintype "passive"))
      (node (ref "L7") (pin "2") (pinfunction "2_2") (pintype "passive"))
      (node (ref "U11") (pin "4") (pinfunction "ANTN_4") (pintype "bidirectional"))
    )
    (net (code "58") (name "Net-(U11-ANTP)") (class "Default")
      (node (ref "C43") (pin "2") (pinfunction "2_2") (pintype "passive"))
      (node (ref "L6") (pin "2") (pinfunction "2_2") (pintype "passive"))
      (node (ref "L8") (pin "1") (pinfunction "1_1") (pintype "passive"))
      (node (ref "U11") (pin "3") (pinfunction "ANTP_3") (pintype "bidirectional"))
    )
    (net (code "59") (name "Net-(U11-ANTP1)") (class "Default")
      (node (ref "C49") (pin "2") (pinfunction "2_2") (pintype "passive"))
      (node (ref "L9") (pin "2") (pinfunction "2_2") (pintype "passive"))
      (node (ref "U11") (pin "5") (pinfunction "ANTP1_5") (pintype "bidirectional"))
    )
    (net (code "60") (name "Net-(U11-CLK16N)") (class "Default")
      (node (ref "C44") (pin "1") (pinfunction "1_1") (pintype "passive"))
      (node (ref "R28") (pin "1") (pinfunction "1_1") (pintype "passive"))
      (node (ref "U11") (pin "27") (pinfunction "CLK16N_27") (pintype "passive"))
    )
    (net (code "61") (name "Net-(U11-CLK16P)") (class "Default")
      (node (ref "C45") (pin "1") (pinfunction "1_1") (pintype "passive"))
      (node (ref "R28") (pin "2") (pinfunction "2_2") (pintype "passive"))
      (node (ref "U11") (pin "28") (pinfunction "CLK16P_28") (pintype "passive"))
    )
    (net (code "62") (name "Net-(U11-CS)") (class "Default")
      (node (ref "J15") (pin "1") (pinfunction "1_1") (pintype "passive"))
      (node (ref "U11") (pin "14") (pinfunction "CS_14") (pintype "input"))
    )
    (net (code "63") (name "Net-(U11-IRQ)") (class "Default")
      (node (ref "J15") (pin "9") (pinfunction "9_9") (pintype "passive"))
      (node (ref "U11") (pin "19") (pinfunction "IRQ_19") (pintype "bidirectional"))
    )
    (net (code "64") (name "Net-(U11-L1)") (class "Default")
      (node (ref "U11") (pin "10") (pinfunction "L1_10") (pintype "input"))
      (node (ref "U11") (pin "9") (pinfunction "L2_9") (pintype "input"))
    )
    (net (code "65") (name "Net-(U11-MISO)") (class "Default")
      (node (ref "J15") (pin "5") (pinfunction "5_5") (pintype "passive"))
      (node (ref "U11") (pin "16") (pinfunction "MISO_16") (pintype "output"))
    )
    (net (code "66") (name "Net-(U11-MOSI)") (class "Default")
      (node (ref "J15") (pin "7") (pinfunction "7_7") (pintype "passive"))
      (node (ref "U11") (pin "17") (pinfunction "MOSI_17") (pintype "input"))
    )
    (net (code "67") (name "Net-(U11-PWRAMP)") (class "Default")
      (node (ref "J15") (pin "11") (pinfunction "11_11") (pintype "passive"))
      (node (ref "U11") (pin "20") (pinfunction "PWRAMP_20") (pintype "bidirectional"))
    )
    (net (code "68") (name "Net-(U11-SCLK)") (class "Default")
      (node (ref "J15") (pin "3") (pinfunction "3_3") (pintype "passive"))
      (node (ref "U11") (pin "15") (pinfunction "SCLK_15") (pintype "input"))
    )
    (net (code "69") (name "Net-(U11-VDD_A1)") (class "Default")
      (node (ref "C46") (pin "1") (pinfunction "1_1") (pintype "passive"))
      (node (ref "U11") (pin "1") (pinfunction "VDD_A1_1") (pintype "power_in"))
    )
    (net (code "70") (name "Net-(U11-VDD_A2)") (class "Default")
      (node (ref "C47") (pin "2") (pinfunction "2_2") (pintype "passive"))
      (node (ref "U11") (pin "7") (pinfunction "VDD_A2_7") (pintype "power_in"))
    )
    (net (code "71") (name "Net-(U11-VDD_IO)") (class "Default")
      (node (ref "C53") (pin "1") (pinfunction "1_1") (pintype "passive"))
      (node (ref "C54") (pin "1") (pinfunction "1_1") (pintype "passive"))
      (node (ref "C55") (pin "1") (pinfunction "1_1") (pintype "passive"))
      (node (ref "R33") (pin "1") (pinfunction "1_1") (pintype "passive"))
      (node (ref "U11") (pin "23") (pinfunction "VDD_IO_23") (pintype "power_in"))
    )
    (net (code "72") (name "Net-(U12-BYPASS)") (class "Default")
      (node (ref "C56") (pin "1") (pinfunction "1_1") (pintype "passive"))
      (node (ref "U12") (pin "4") (pinfunction "BYPASS_4") (pintype "power_in"))
    )
    (net (code "73") (name "Net-(U12-EN)") (class "Default")
      (node (ref "C57") (pin "1") (pinfunction "1_1") (pintype "passive"))
      (node (ref "R32") (pin "2") (pinfunction "2_2") (pintype "passive"))
      (node (ref "U12") (pin "1") (pinfunction "VIN_1") (pintype "power_in"))
      (node (ref "U12") (pin "3") (pinfunction "EN_3") (pintype "input"))
    )
    (net (code "74") (name "Net-(U12-VOUT)") (class "Default")
      (node (ref "C50") (pin "1") (pinfunction "1_1") (pintype "passive"))
      (node (ref "C51") (pin "1") (pinfunction "1_1") (pintype "passive"))
      (node (ref "C52") (pin "1") (pinfunction "1_1") (pintype "passive"))
      (node (ref "U12") (pin "5") (pinfunction "VOUT_5") (pintype "power_in"))
      (node (ref "X3") (pin "4") (pinfunction "VDD_4") (pintype "power_in"))
    )
    (net (code "75") (name "Net-(U13-ANTN)") (class "Default")
      (node (ref "C58") (pin "2") (pinfunction "2_2") (pintype "passive"))
      (node (ref "L11") (pin "2") (pinfunction "2_2") (pintype "passive"))
      (node (ref "U13") (pin "4") (pinfunction "ANTN_4") (pintype "bidirectional"))
    )
    (net (code "76") (name "Net-(U13-ANTP)") (class "Default")
      (node (ref "C59") (pin "2") (pinfunction "2_2") (pintype "passive"))
      (node (ref "L10") (pin "2") (pinfunction "2_2") (pintype "passive"))
      (node (ref "L12") (pin "1") (pinfunction "1_1") (pintype "passive"))
      (node (ref "U13") (pin "3") (pinfunction "ANTP_3") (pintype "bidirectional"))
    )
    (net (code "77") (name "Net-(U13-ANTP1)") (class "Default")
      (node (ref "C65") (pin "2") (pinfunction "2_2") (pintype "passive"))
      (node (ref "L13") (pin "2") (pinfunction "2_2") (pintype "passive"))
      (node (ref "U13") (pin "5") (pinfunction "ANTP1_5") (pintype "bidirectional"))
    )
    (net (code "78") (name "Net-(U13-CLK16N)") (class "Default")
      (node (ref "C60") (pin "1") (pinfunction "1_1") (pintype "passive"))
      (node (ref "R34") (pin "1") (pinfunction "1_1") (pintype "passive"))
      (node (ref "U13") (pin "27") (pinfunction "CLK16N_27") (pintype "passive"))
    )
    (net (code "79") (name "Net-(U13-CLK16P)") (class "Default")
      (node (ref "C61") (pin "1") (pinfunction "1_1") (pintype "passive"))
      (node (ref "R34") (pin "2") (pinfunction "2_2") (pintype "passive"))
      (node (ref "U13") (pin "28") (pinfunction "CLK16P_28") (pintype "passive"))
    )
    (net (code "80") (name "Net-(U13-CS)") (class "Default")
      (node (ref "J19") (pin "1") (pinfunction "1_1") (pintype "passive"))
      (node (ref "U13") (pin "14") (pinfunction "CS_14") (pintype "input"))
    )
    (net (code "81") (name "Net-(U13-IRQ)") (class "Default")
      (node (ref "J19") (pin "9") (pinfunction "9_9") (pintype "passive"))
      (node (ref "U13") (pin "19") (pinfunction "IRQ_19") (pintype "bidirectional"))
    )
    (net (code "82") (name "Net-(U13-L1)") (class "Default")
      (node (ref "U13") (pin "10") (pinfunction "L1_10") (pintype "input"))
      (node (ref "U13") (pin "9") (pinfunction "L2_9") (pintype "input"))
    )
    (net (code "83") (name "Net-(U13-MISO)") (class "Default")
      (node (ref "J19") (pin "5") (pinfunction "5_5") (pintype "passive"))
      (node (ref "U13") (pin "16") (pinfunction "MISO_16") (pintype "output"))
    )
    (net (code "84") (name "Net-(U13-MOSI)") (class "Default")
      (node (ref "J19") (pin "7") (pinfunction "7_7") (pintype "passive"))
      (node (ref "U13") (pin "17") (pinfunction "MOSI_17") (pintype "input"))
    )
    (net (code "85") (name "Net-(U13-PWRAMP)") (class "Default")
      (node (ref "J19") (pin "11") (pinfunction "11_11") (pintype "passive"))
      (node (ref "U13") (pin "20") (pinfunction "PWRAMP_20") (pintype "bidirectional"))
    )
    (net (code "86") (name "Net-(U13-SCLK)") (class "Default")
      (node (ref "J19") (pin "3") (pinfunction "3_3") (pintype "passive"))
      (node (ref "U13") (pin "15") (pinfunction "SCLK_15") (pintype "input"))
    )
    (net (code "87") (name "Net-(U13-VDD_A1)") (class "Default")
      (node (ref "C62") (pin "1") (pinfunction "1_1") (pintype "passive"))
      (node (ref "U13") (pin "1") (pinfunction "VDD_A1_1") (pintype "power_in"))
    )
    (net (code "88") (name "Net-(U13-VDD_A2)") (class "Default")
      (node (ref "C63") (pin "2") (pinfunction "2_2") (pintype "passive"))
      (node (ref "U13") (pin "7") (pinfunction "VDD_A2_7") (pintype "power_in"))
    )
    (net (code "89") (name "Net-(U13-VDD_IO)") (class "Default")
      (node (ref "C69") (pin "1") (pinfunction "1_1") (pintype "passive"))
      (node (ref "C70") (pin "1") (pinfunction "1_1") (pintype "passive"))
      (node (ref "C71") (pin "1") (pinfunction "1_1") (pintype "passive"))
      (node (ref "R40") (pin "1") (pinfunction "1_1") (pintype "passive"))
      (node (ref "U13") (pin "23") (pinfunction "VDD_IO_23") (pintype "power_in"))
    )
    (net (code "90") (name "Net-(U14-BYPASS)") (class "Default")
      (node (ref "C72") (pin "1") (pinfunction "1_1") (pintype "passive"))
      (node (ref "U14") (pin "4") (pinfunction "BYPASS_4") (pintype "power_in"))
    )
    (net (code "91") (name "Net-(U14-EN)") (class "Default")
      (node (ref "C73") (pin "1") (pinfunction "1_1") (pintype "passive"))
      (node (ref "R39") (pin "2") (pinfunction "2_2") (pintype "passive"))
      (node (ref "U14") (pin "1") (pinfunction "VIN_1") (pintype "power_in"))
      (node (ref "U14") (pin "3") (pinfunction "EN_3") (pintype "input"))
    )
    (net (code "92") (name "Net-(U14-VOUT)") (class "Default")
      (node (ref "C66") (pin "1") (pinfunction "1_1") (pintype "passive"))
      (node (ref "C67") (pin "1") (pinfunction "1_1") (pintype "passive"))
      (node (ref "C68") (pin "1") (pinfunction "1_1") (pintype "passive"))
      (node (ref "U14") (pin "5") (pinfunction "VOUT_5") (pintype "power_in"))
      (node (ref "X4") (pin "4") (pinfunction "VDD_4") (pintype "power_in"))
    )
    (net (code "93") (name "Net-(X3-OUT)") (class "Default")
      (node (ref "C45") (pin "2") (pinfunction "2_2") (pintype "passive"))
      (node (ref "X3") (pin "3") (pinfunction "OUT_3") (pintype "output"))
    )
    (net (code "94") (name "Net-(X4-OUT)") (class "Default")
      (node (ref "C61") (pin "2") (pinfunction "2_2") (pintype "passive"))
      (node (ref "X4") (pin "3") (pinfunction "OUT_3") (pintype "output"))
    )
    (net (code "95") (name "OPD_ISET") (class "Default")
      (node (ref "R24") (pin "1") (pinfunction "1_1") (pintype "passive"))
      (node (ref "R36") (pin "2") (pinfunction "2_2") (pintype "passive"))
      (node (ref "TP14") (pin "1") (pinfunction "1_1") (pintype "passive"))
      (node (ref "U1") (pin "5") (pinfunction "SET_5") (pintype "input"))
    )
    (net (code "96") (name "OPD_ISET_IN") (class "Default")
      (node (ref "R24") (pin "2") (pinfunction "2_2") (pintype "passive"))
      (node (ref "U7") (pin "27") (pinfunction "PB1_27") (pintype "bidirectional"))
    )
    (net (code "97") (name "OPD_PWR") (class "Default")
      (node (ref "C4") (pin "1") (pinfunction "1_1") (pintype "passive"))
      (node (ref "J6") (pin "15") (pinfunction "15_15") (pintype "passive"))
      (node (ref "J6") (pin "16") (pinfunction "16_16") (pintype "passive"))
      (node (ref "JP1") (pin "5") (pinfunction "5_5") (pintype "passive"))
      (node (ref "JP1") (pin "6") (pinfunction "6_6") (pintype "passive"))
      (node (ref "R11") (pin "1") (pinfunction "1_1") (pintype "passive"))
      (node (ref "R4") (pin "2") (pinfunction "2_2") (pintype "passive"))
      (node (ref "R8") (pin "1") (pinfunction "1_1") (pintype "passive"))
      (node (ref "U1") (pin "7") (pinfunction "OUT_2_7") (pintype "power_in"))
      (node (ref "U1") (pin "8") (pinfunction "OUT_8") (pintype "power_in"))
    )
    (net (code "98") (name "OPD_SCL") (class "Default")
      (node (ref "J6") (pin "13") (pinfunction "13_13") (pintype "passive"))
      (node (ref "J6") (pin "14") (pinfunction "14_14") (pintype "passive"))
      (node (ref "JP1") (pin "3") (pinfunction "3_3") (pintype "passive"))
      (node (ref "JP1") (pin "4") (pinfunction "4_4") (pintype "passive"))
      (node (ref "R8") (pin "2") (pinfunction "2_2") (pintype "passive"))
      (node (ref "U7") (pin "61") (pinfunction "PB8_61") (pintype "bidirectional"))
    )
    (net (code "99") (name "OPD_SDA") (class "Default")
      (node (ref "J6") (pin "11") (pinfunction "11_11") (pintype "passive"))
      (node (ref "J6") (pin "12") (pinfunction "12_12") (pintype "passive"))
      (node (ref "JP1") (pin "1") (pinfunction "1_1") (pintype "passive"))
      (node (ref "JP1") (pin "2") (pinfunction "2_2") (pintype "passive"))
      (node (ref "R11") (pin "2") (pinfunction "2_2") (pintype "passive"))
      (node (ref "U7") (pin "62") (pinfunction "PB9_62") (pintype "bidirectional"))
    )
    (net (code "100") (name "OPD_~{FAULT}") (class "Default")
      (node (ref "R16") (pin "1") (pinfunction "1_1") (pintype "passive"))
      (node (ref "TP8") (pin "1") (pinfunction "1_1") (pintype "passive"))
      (node (ref "U1") (pin "6") (pinfunction "~{FAULT}_6") (pintype "output"))
      (node (ref "U7") (pin "55") (pinfunction "PB3_55") (pintype "bidirectional"))
    )
    (net (code "101") (name "OSC32_IN") (class "Default")
      (node (ref "U7") (pin "3") (pinfunction "PC14-OSC32_IN_3") (pintype "bidirectional"))
    )
    (net (code "102") (name "OSC32_OUT") (class "Default")
      (node (ref "U7") (pin "4") (pinfunction "PC15-OSC32_OUT_4") (pintype "bidirectional"))
    )
    (net (code "103") (name "PA1") (class "Default")
      (node (ref "TP5") (pin "1") (pinfunction "1_1") (pintype "passive"))
      (node (ref "U7") (pin "15") (pinfunction "PA1_15") (pintype "bidirectional"))
    )
    (net (code "104") (name "PA15") (class "Default")
      (node (ref "TP6") (pin "1") (pinfunction "1_1") (pintype "passive"))
      (node (ref "U7") (pin "50") (pinfunction "PA15_50") (pintype "bidirectional"))
    )
    (net (code "105") (name "PB10") (class "Default")
      (node (ref "TP4") (pin "1") (pinfunction "1_1") (pintype "passive"))
      (node (ref "U7") (pin "29") (pinfunction "PB10_29") (pintype "bidirectional"))
    )
    (net (code "106") (name "PB12") (class "Default")
      (node (ref "JP11") (pin "1") (pinfunction "1_1") (pintype "passive"))
      (node (ref "U7") (pin "33") (pinfunction "PB12_33") (pintype "bidirectional"))
    )
    (net (code "107") (name "PC0") (class "Default")
      (node (ref "JP11") (pin "9") (pinfunction "9_9") (pintype "passive"))
      (node (ref "U7") (pin "8") (pinfunction "PC0_8") (pintype "bidirectional"))
    )
    (net (code "108") (name "PC1") (class "Default")
      (node (ref "JP11") (pin "10") (pinfunction "10_10") (pintype "passive"))
      (node (ref "U7") (pin "9") (pinfunction "PC1_9") (pintype "bidirectional"))
    )
    (net (code "109") (name "PC2") (class "Default")
      (node (ref "JP11") (pin "8") (pinfunction "8_8") (pintype "passive"))
      (node (ref "U7") (pin "10") (pinfunction "PC2_10") (pintype "bidirectional"))
    )
    (net (code "110") (name "PC3") (class "Default")
      (node (ref "JP11") (pin "6") (pinfunction "6_6") (pintype "passive"))
      (node (ref "U7") (pin "11") (pinfunction "PC3_11") (pintype "bidirectional"))
    )
    (net (code "111") (name "PC4") (class "Default")
      (node (ref "JP11") (pin "4") (pinfunction "4_4") (pintype "passive"))
      (node (ref "U7") (pin "24") (pinfunction "PC4_24") (pintype "bidirectional"))
    )
    (net (code "112") (name "PC5") (class "Default")
      (node (ref "JP11") (pin "2") (pinfunction "2_2") (pintype "passive"))
      (node (ref "U7") (pin "25") (pinfunction "PC5_25") (pintype "bidirectional"))
    )
    (net (code "113") (name "RADIO1_CS") (class "Default")
      (node (ref "J15") (pin "2") (pinfunction "2_2") (pintype "passive"))
      (node (ref "U7") (pin "37") (pinfunction "PC6_37") (pintype "bidirectional"))
    )
    (net (code "114") (name "RADIO1_IRQ") (class "Default")
      (node (ref "J15") (pin "10") (pinfunction "10_10") (pintype "passive"))
      (node (ref "U7") (pin "20") (pinfunction "PA4_20") (pintype "bidirectional"))
    )
    (net (code "115") (name "RADIO1_PTT") (class "Default")
      (node (ref "J15") (pin "12") (pinfunction "12_12") (pintype "passive"))
    )
    (net (code "116") (name "RADIO2_CS") (class "Default")
      (node (ref "J19") (pin "2") (pinfunction "2_2") (pintype "passive"))
      (node (ref "U7") (pin "38") (pinfunction "PC7_38") (pintype "bidirectional"))
    )
    (net (code "117") (name "RADIO2_IRQ") (class "Default")
      (node (ref "J19") (pin "10") (pinfunction "10_10") (pintype "passive"))
      (node (ref "U7") (pin "41") (pinfunction "PA8_41") (pintype "bidirectional"))
    )
    (net (code "118") (name "RADIO2_PTT") (class "Default")
      (node (ref "J19") (pin "12") (pinfunction "12_12") (pintype "passive"))
    )
    (net (code "119") (name "SDIO_CK") (class "Default")
      (node (ref "R14") (pin "9") (pinfunction "99_9") (pintype "passive"))
      (node (ref "TP7") (pin "1") (pinfunction "1_1") (pintype "passive"))
      (node (ref "U7") (pin "53") (pinfunction "PC12_53") (pintype "bidirectional"))
      (node (ref "U9") (pin "M6") (pinfunction "SCK_M6") (pintype "input"))
    )
    (net (code "120") (name "SDIO_CMD") (class "Default")
      (node (ref "R14") (pin "2") (pinfunction "22_2") (pintype "passive"))
      (node (ref "U7") (pin "54") (pinfunction "PD2_54") (pintype "bidirectional"))
      (node (ref "U9") (pin "M5") (pinfunction "CMD_M5") (pintype "input"))
    )
    (net (code "121") (name "SDIO_D0") (class "Default")
      (node (ref "R15") (pin "1") (pinfunction "11_1") (pintype "passive"))
      (node (ref "U7") (pin "39") (pinfunction "PC8_39") (pintype "bidirectional"))
      (node (ref "U9") (pin "A3") (pinfunction "D0_A3") (pintype "input"))
    )
    (net (code "122") (name "SDIO_D1") (class "Default")
      (node (ref "R15") (pin "9") (pinfunction "99_9") (pintype "passive"))
      (node (ref "U7") (pin "40") (pinfunction "PC9_40") (pintype "bidirectional"))
      (node (ref "U9") (pin "A4") (pinfunction "D1_A4") (pintype "input"))
    )
    (net (code "123") (name "SDIO_D2") (class "Default")
      (node (ref "R15") (pin "2") (pinfunction "22_2") (pintype "passive"))
      (node (ref "U7") (pin "51") (pinfunction "PC10_51") (pintype "bidirectional"))
      (node (ref "U9") (pin "A5") (pinfunction "D2_A5") (pintype "input"))
    )
    (net (code "124") (name "SDIO_D3") (class "Default")
      (node (ref "R14") (pin "7") (pinfunction "77_7") (pintype "passive"))
      (node (ref "U7") (pin "52") (pinfunction "PC11_52") (pintype "bidirectional"))
      (node (ref "U9") (pin "A1") (pinfunction "D3_A1") (pintype "input"))
      (node (ref "U9") (pin "B2") (pinfunction "D3_B2") (pintype "input"))
    )
    (net (code "125") (name "SDIO_D4") (class "Default")
      (node (ref "R14") (pin "6") (pinfunction "66_6") (pintype "passive"))
      (node (ref "U9") (pin "A2") (pinfunction "D4_A2") (pintype "input"))
      (node (ref "U9") (pin "B3") (pinfunction "D4_B3") (pintype "input"))
    )
    (net (code "126") (name "SDIO_D5") (class "Default")
      (node (ref "R14") (pin "8") (pinfunction "88_8") (pintype "passive"))
      (node (ref "U9") (pin "B4") (pinfunction "D5_B4") (pintype "input"))
      (node (ref "U9") (pin "C3") (pinfunction "D5_C3") (pintype "input"))
      (node (ref "U9") (pin "D3") (pinfunction "D5_D3") (pintype "input"))
    )
    (net (code "127") (name "SDIO_D6") (class "Default")
      (node (ref "R14") (pin "4") (pinfunction "44_4") (pintype "passive"))
      (node (ref "U9") (pin "B5") (pinfunction "D6_B5") (pintype "bidirectional"))
      (node (ref "U9") (pin "C5") (pinfunction "D6_C5") (pintype "bidirectional"))
    )
    (net (code "128") (name "SDIO_D7") (class "Default")
      (node (ref "R15") (pin "3") (pinfunction "33_3") (pintype "passive"))
      (node (ref "U9") (pin "B6") (pinfunction "D7_B6") (pintype "input"))
      (node (ref "U9") (pin "C7") (pinfunction "D7_C7") (pintype "input"))
    )
    (net (code "129") (name "SDIO_RST") (class "Default")
      (node (ref "R14") (pin "3") (pinfunction "33_3") (pintype "passive"))
      (node (ref "U9") (pin "K5") (pinfunction "~{RST}_K5") (pintype "input"))
    )
    (net (code "130") (name "SPARE1") (class "Default")
      (node (ref "J6") (pin "10") (pinfunction "10_10") (pintype "passive"))
      (node (ref "J6") (pin "9") (pinfunction "9_9") (pintype "passive"))
      (node (ref "JP2") (pin "5") (pinfunction "5_5") (pintype "passive"))
    )
    (net (code "131") (name "SPARE2") (class "Default")
      (node (ref "J6") (pin "7") (pinfunction "7_7") (pintype "passive"))
      (node (ref "J6") (pin "8") (pinfunction "8_8") (pintype "passive"))
      (node (ref "JP2") (pin "4") (pinfunction "4_4") (pintype "passive"))
    )
    (net (code "132") (name "SPARE3") (class "Default")
      (node (ref "J6") (pin "5") (pinfunction "5_5") (pintype "passive"))
      (node (ref "J6") (pin "6") (pinfunction "6_6") (pintype "passive"))
      (node (ref "JP2") (pin "3") (pinfunction "3_3") (pintype "passive"))
    )
    (net (code "133") (name "SPARE4") (class "Default")
      (node (ref "J6") (pin "3") (pinfunction "3_3") (pintype "passive"))
      (node (ref "J6") (pin "4") (pinfunction "4_4") (pintype "passive"))
      (node (ref "JP2") (pin "2") (pinfunction "2_2") (pintype "passive"))
    )
    (net (code "134") (name "SPARE5") (class "Default")
      (node (ref "J6") (pin "1") (pinfunction "1_1") (pintype "passive"))
      (node (ref "J6") (pin "2") (pinfunction "2_2") (pintype "passive"))
      (node (ref "JP2") (pin "1") (pinfunction "1_1") (pintype "passive"))
    )
    (net (code "135") (name "SPI1_MISO") (class "Default")
      (node (ref "J15") (pin "6") (pinfunction "6_6") (pintype "passive"))
      (node (ref "J19") (pin "6") (pinfunction "6_6") (pintype "passive"))
      (node (ref "TP22") (pin "1") (pinfunction "1_1") (pintype "passive"))
      (node (ref "U7") (pin "22") (pinfunction "PA6_22") (pintype "bidirectional"))
    )
    (net (code "136") (name "SPI1_MOSI") (class "Default")
      (node (ref "J15") (pin "8") (pinfunction "8_8") (pintype "passive"))
      (node (ref "J19") (pin "8") (pinfunction "8_8") (pintype "passive"))
      (node (ref "TP18") (pin "1") (pinfunction "1_1") (pintype "passive"))
      (node (ref "U7") (pin "23") (pinfunction "PA7_23") (pintype "bidirectional"))
    )
    (net (code "137") (name "SPI1_SCK") (class "Default")
      (node (ref "J15") (pin "4") (pinfunction "4_4") (pintype "passive"))
      (node (ref "J19") (pin "4") (pinfunction "4_4") (pintype "passive"))
      (node (ref "TP23") (pin "1") (pinfunction "1_1") (pintype "passive"))
      (node (ref "U7") (pin "21") (pinfunction "PA5_21") (pintype "bidirectional"))
    )
    (net (code "138") (name "SPI2_MISO") (class "Default")
      (node (ref "JP11") (pin "5") (pinfunction "5_5") (pintype "passive"))
      (node (ref "U7") (pin "35") (pinfunction "PB14_35") (pintype "bidirectional"))
    )
    (net (code "139") (name "SPI2_MOSI") (class "Default")
      (node (ref "JP11") (pin "7") (pinfunction "7_7") (pintype "passive"))
      (node (ref "U7") (pin "36") (pinfunction "PB15_36") (pintype "bidirectional"))
    )
    (net (code "140") (name "SPI2_SCK") (class "Default")
      (node (ref "JP11") (pin "3") (pinfunction "3_3") (pintype "passive"))
      (node (ref "U7") (pin "34") (pinfunction "PB13_34") (pintype "bidirectional"))
    )
    (net (code "141") (name "SWCLK") (class "Default")
      (node (ref "J7") (pin "4") (pinfunction "SWDCLK/TCK_4") (pintype "passive"))
      (node (ref "U7") (pin "49") (pinfunction "PA14_49") (pintype "bidirectional"))
    )
    (net (code "142") (name "SWDIO") (class "Default")
      (node (ref "J7") (pin "2") (pinfunction "SWDIO/TMS_2") (pintype "passive"))
      (node (ref "U7") (pin "46") (pinfunction "PA13_46") (pintype "bidirectional"))
    )
    (net (code "143") (name "SYSCLK1") (class "Default")
      (node (ref "J8") (pin "FEED") (pinfunction "SIGNAL_FEED") (pintype "bidirectional"))
      (node (ref "U11") (pin "13") (pinfunction "SYSCLK_13") (pintype "bidirectional"))
    )
    (net (code "144") (name "USART2_RX") (class "Default")
      (node (ref "J5") (pin "P$2") (pinfunction "TXO_P$2") (pintype "passive"))
      (node (ref "U7") (pin "17") (pinfunction "PA3_17") (pintype "bidirectional"))
    )
    (net (code "145") (name "USART2_TX") (class "Default")
      (node (ref "J5") (pin "P$3") (pinfunction "RXI_P$3") (pintype "passive"))
      (node (ref "U7") (pin "16") (pinfunction "PA2_16") (pintype "bidirectional"))
    )
    (net (code "146") (name "VBUS") (class "Default")
      (node (ref "C1") (pin "1") (pinfunction "1_1") (pintype "passive"))
      (node (ref "J6") (pin "21") (pinfunction "21_21") (pintype "passive"))
      (node (ref "J6") (pin "22") (pinfunction "22_22") (pintype "passive"))
      (node (ref "J6") (pin "23") (pinfunction "23_23") (pintype "passive"))
      (node (ref "J6") (pin "24") (pinfunction "24_24") (pintype "passive"))
      (node (ref "J6") (pin "25") (pinfunction "25_25") (pintype "passive"))
      (node (ref "J6") (pin "26") (pinfunction "26_26") (pintype "passive"))
      (node (ref "JP10") (pin "1") (pinfunction "1_1") (pintype "passive"))
      (node (ref "JP10") (pin "2") (pinfunction "2_2") (pintype "passive"))
      (node (ref "JP10") (pin "3") (pinfunction "3_3") (pintype "passive"))
      (node (ref "JP10") (pin "4") (pinfunction "4_4") (pintype "passive"))
      (node (ref "R5") (pin "2") (pinfunction "2_2") (pintype "passive"))
      (node (ref "U4") (pin "4") (pinfunction "VIN_4") (pintype "power_in"))
    )
    (net (code "147") (name "VBUSP") (class "Default")
      (node (ref "C10") (pin "1") (pinfunction "1_1") (pintype "passive"))
      (node (ref "C7") (pin "1") (pinfunction "1_1") (pintype "passive"))
      (node (ref "JP4") (pin "1") (pinfunction "1_1") (pintype "passive"))
      (node (ref "JP4") (pin "2") (pinfunction "2_2") (pintype "passive"))
      (node (ref "JP8") (pin "1") (pinfunction "1_1") (pintype "passive"))
      (node (ref "R1") (pin "2") (pinfunction "2_2") (pintype "passive"))
      (node (ref "R7") (pin "2") (pinfunction "2_2") (pintype "passive"))
      (node (ref "TP20") (pin "1") (pinfunction "1_1") (pintype "passive"))
      (node (ref "U4") (pin "5") (pinfunction "VOUT_5") (pintype "power_in"))
      (node (ref "U5") (pin "2") (pinfunction "VIN_2") (pintype "power_in"))
      (node (ref "U5") (pin "3") (pinfunction "VIN_3") (pintype "power_in"))
      (node (ref "U5") (pin "4") (pinfunction "EN_4") (pintype "input"))
      (node (ref "U5") (pin "8") (pinfunction "VIN_8") (pintype "power_in"))
    )
    (net (code "148") (name "VCAP") (class "Default")
      (node (ref "C14") (pin "1") (pinfunction "1_1") (pintype "passive"))
      (node (ref "U7") (pin "30") (pinfunction "VCAP_1_30") (pintype "bidirectional"))
    )
    (net (code "149") (name "VDDI") (class "Default")
      (node (ref "C19") (pin "1") (pinfunction "1_1") (pintype "passive"))
      (node (ref "C21") (pin "1") (pinfunction "1_1") (pintype "passive"))
      (node (ref "U9") (pin "C1") (pinfunction "VDDI_C1") (pintype "power_in"))
      (node (ref "U9") (pin "C2") (pinfunction "VDDI_C2") (pintype "power_in"))
    )
    (net (code "150") (name "WDT") (class "Default")
      (node (ref "R3") (pin "2") (pinfunction "2_2") (pintype "passive"))
      (node (ref "TP3") (pin "1") (pinfunction "1_1") (pintype "passive"))
      (node (ref "U6") (pin "1") (pinfunction "WDI_1") (pintype "input"))
      (node (ref "U7") (pin "14") (pinfunction "PA0_14") (pintype "bidirectional"))
    )
    (net (code "151") (name "unconnected-(J5-CTS-PadP$5)") (class "Default")
      (node (ref "J5") (pin "P$5") (pinfunction "CTS_P$5") (pintype "passive"))
    )
    (net (code "152") (name "unconnected-(J5-DTR-PadP$1)") (class "Default")
      (node (ref "J5") (pin "P$1") (pinfunction "DTR_P$1") (pintype "passive"))
    )
    (net (code "153") (name "unconnected-(J7-NC{slash}TDI-Pad8)") (class "Default")
      (node (ref "J7") (pin "8") (pinfunction "NC/TDI_8") (pintype "passive"))
    )
    (net (code "154") (name "unconnected-(J7-SWO{slash}TDO-Pad6)") (class "Default")
      (node (ref "J7") (pin "6") (pinfunction "SWO/TDO_6") (pintype "passive"))
    )
    (net (code "155") (name "unconnected-(JP2-Pad6)") (class "Default")
      (node (ref "JP2") (pin "6") (pinfunction "6_6") (pintype "passive"))
    )
    (net (code "156") (name "unconnected-(R15-44-Pad4)") (class "Default")
      (node (ref "R15") (pin "4") (pinfunction "44_4") (pintype "passive"))
    )
    (net (code "157") (name "unconnected-(R15-66-Pad6)") (class "Default")
      (node (ref "R15") (pin "6") (pinfunction "66_6") (pintype "passive"))
    )
    (net (code "158") (name "unconnected-(R15-77-Pad7)") (class "Default")
      (node (ref "R15") (pin "7") (pinfunction "77_7") (pintype "passive"))
    )
    (net (code "159") (name "unconnected-(R15-88-Pad8)") (class "Default")
      (node (ref "R15") (pin "8") (pinfunction "88_8") (pintype "passive"))
    )
    (net (code "160") (name "unconnected-(U4-DV{slash}DT-Pad2)") (class "Default")
      (node (ref "U4") (pin "2") (pinfunction "DV/DT_2") (pintype "bidirectional"))
    )
    (net (code "161") (name "unconnected-(U4-OVLO-Pad8)") (class "Default")
      (node (ref "U4") (pin "8") (pinfunction "OVLO_8") (pintype "bidirectional"))
    )
    (net (code "162") (name "unconnected-(U6-NC-Pad3)") (class "Default")
      (node (ref "U6") (pin "3") (pinfunction "NC_3") (pintype "no_connect"))
    )
    (net (code "163") (name "unconnected-(U11-ANTSEL-Pad21)") (class "Default")
      (node (ref "U11") (pin "21") (pinfunction "ANTSEL_21") (pintype "bidirectional"))
    )
    (net (code "164") (name "unconnected-(U11-DATA-Pad11)") (class "Default")
      (node (ref "U11") (pin "11") (pinfunction "DATA_11") (pintype "bidirectional"))
    )
    (net (code "165") (name "unconnected-(U11-DCLK-Pad12)") (class "Default")
      (node (ref "U11") (pin "12") (pinfunction "DCLK_12") (pintype "bidirectional"))
    )
    (net (code "166") (name "unconnected-(U11-FILT-Pad8)") (class "Default")
      (node (ref "U11") (pin "8") (pinfunction "FILT_8") (pintype "output"))
    )
    (net (code "167") (name "unconnected-(U13-ANTSEL-Pad21)") (class "Default")
      (node (ref "U13") (pin "21") (pinfunction "ANTSEL_21") (pintype "bidirectional"))
    )
    (net (code "168") (name "unconnected-(U13-DATA-Pad11)") (class "Default")
      (node (ref "U13") (pin "11") (pinfunction "DATA_11") (pintype "bidirectional"))
    )
    (net (code "169") (name "unconnected-(U13-DCLK-Pad12)") (class "Default")
      (node (ref "U13") (pin "12") (pinfunction "DCLK_12") (pintype "bidirectional"))
    )
    (net (code "170") (name "unconnected-(U13-FILT-Pad8)") (class "Default")
      (node (ref "U13") (pin "8") (pinfunction "FILT_8") (pintype "output"))
    )
    (net (code "171") (name "unconnected-(X3-VCTRL-Pad1)") (class "Default")
      (node (ref "X3") (pin "1") (pinfunction "VCTRL_1") (pintype "input"))
    )
    (net (code "172") (name "unconnected-(X4-VCTRL-Pad1)") (class "Default")
      (node (ref "X4") (pin "1") (pinfunction "VCTRL_1") (pintype "input"))
    )
    (net (code "173") (name "~{OPD_ENABLE}") (class "Default")
      (node (ref "D4") (pin "C") (pinfunction "C_C") (pintype "passive"))
      (node (ref "TP13") (pin "1") (pinfunction "1_1") (pintype "passive"))
      (node (ref "U1") (pin "3") (pinfunction "~{ON}_3") (pintype "input"))
      (node (ref "U7") (pin "28") (pinfunction "PB2_28") (pintype "bidirectional"))
    )
    (net (code "174") (name "~{SD}") (class "Default")
      (node (ref "J6") (pin "39") (pinfunction "39_39") (pintype "passive"))
      (node (ref "J6") (pin "40") (pinfunction "40_40") (pintype "passive"))
      (node (ref "JP10") (pin "10") (pinfunction "10_10") (pintype "passive"))
      (node (ref "JP10") (pin "9") (pinfunction "9_9") (pintype "passive"))
      (node (ref "R13") (pin "2") (pinfunction "2_2") (pintype "passive"))
      (node (ref "U6") (pin "7") (pinfunction "~{WDO}_7") (pintype "output"))
    )
  )
)
